# PowerBoard_V04.net
KiCad netlist of a schematic drawn in Altium Designer
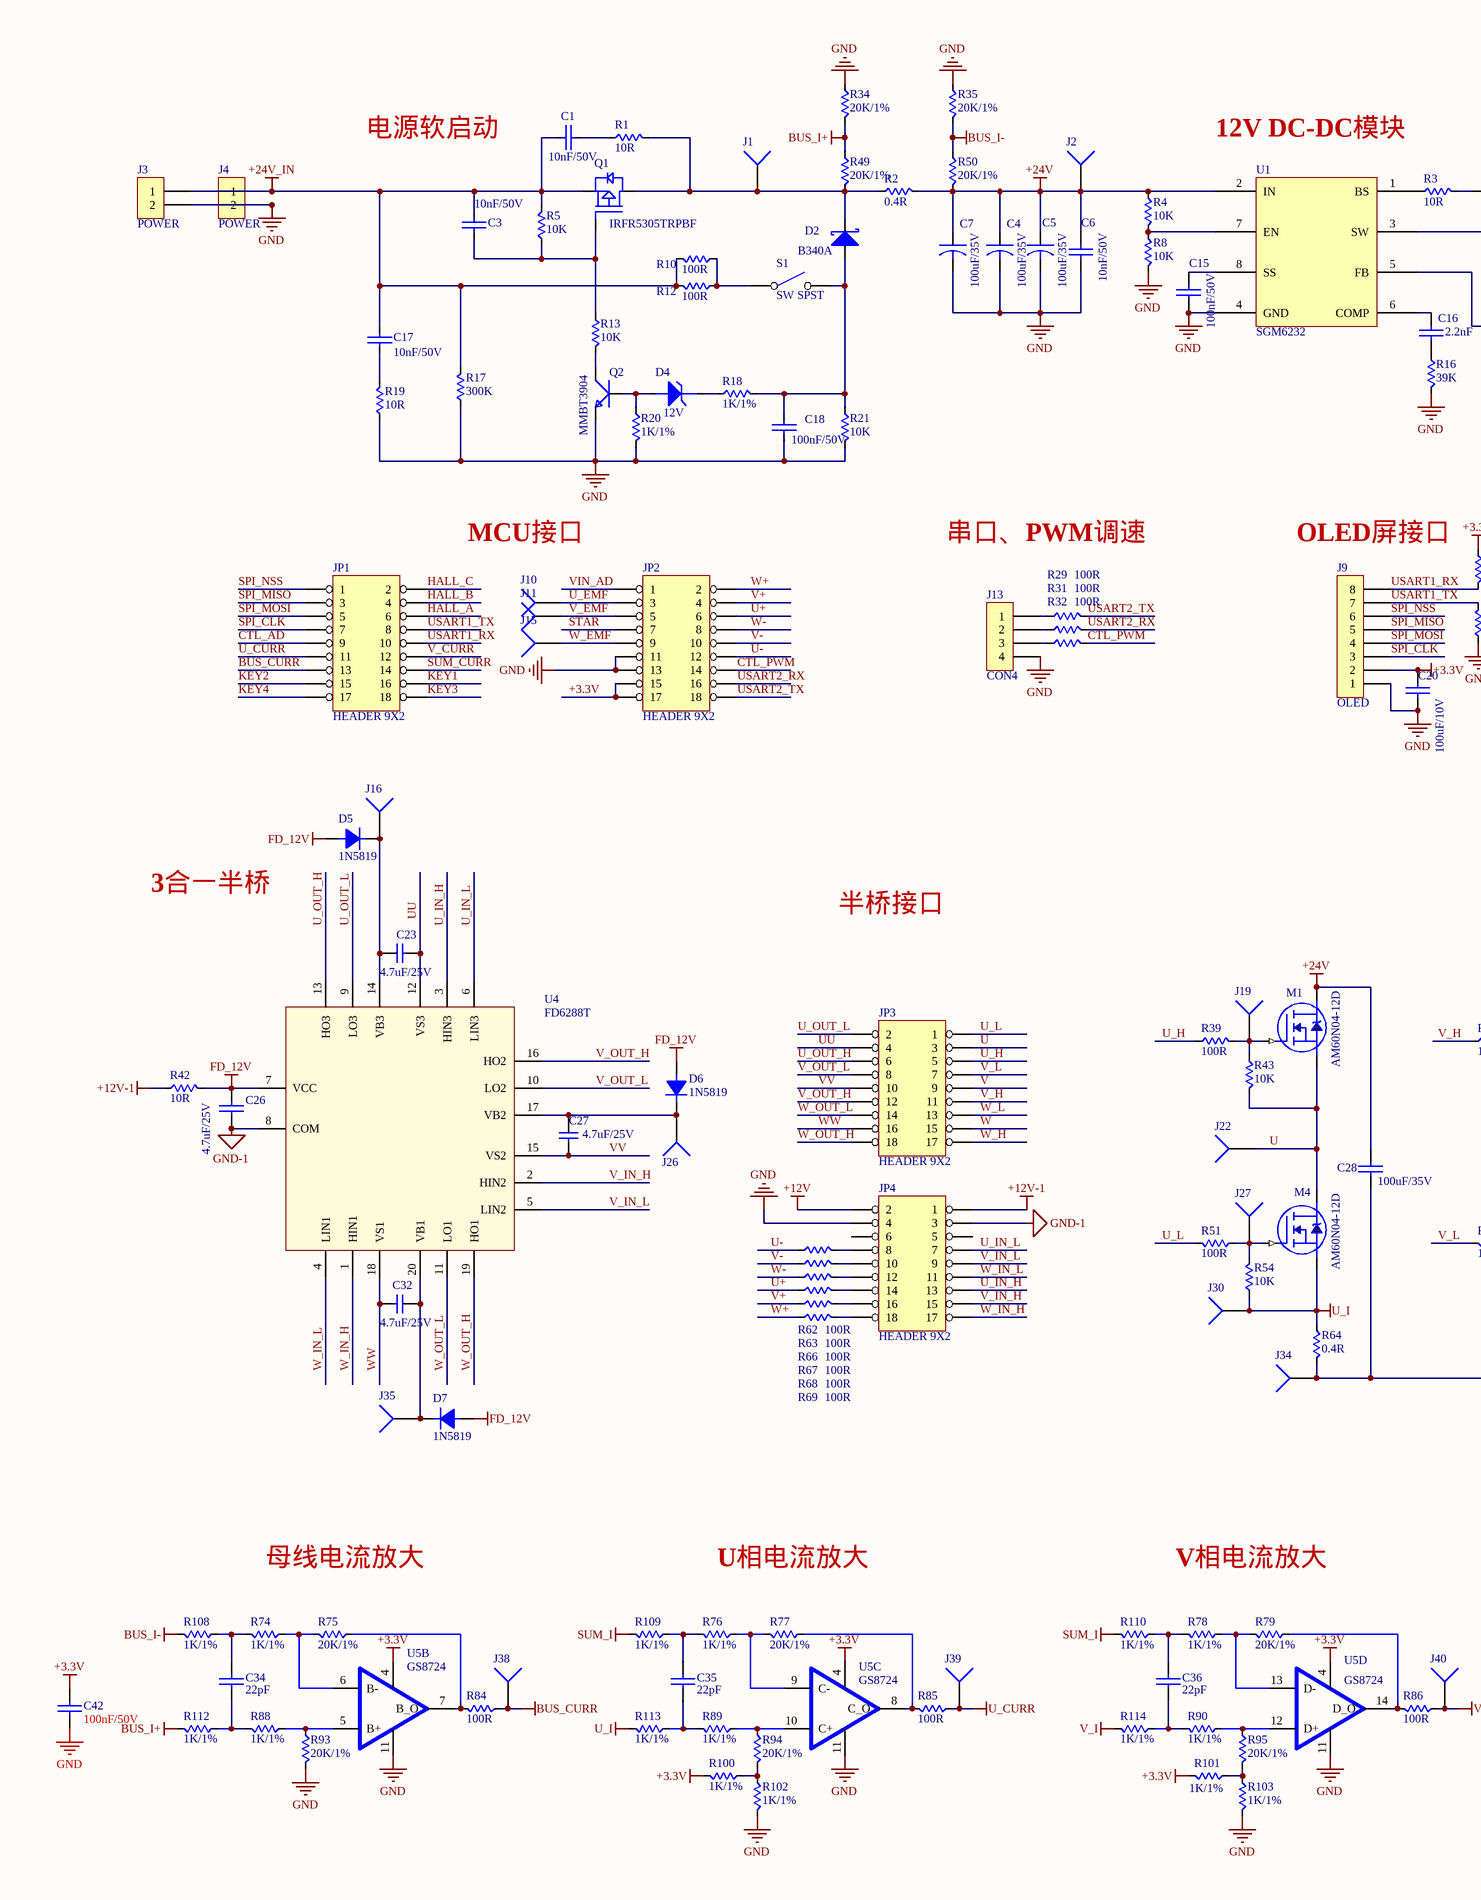
[diagram p0: PowerBoard V04.SchDoc, left]
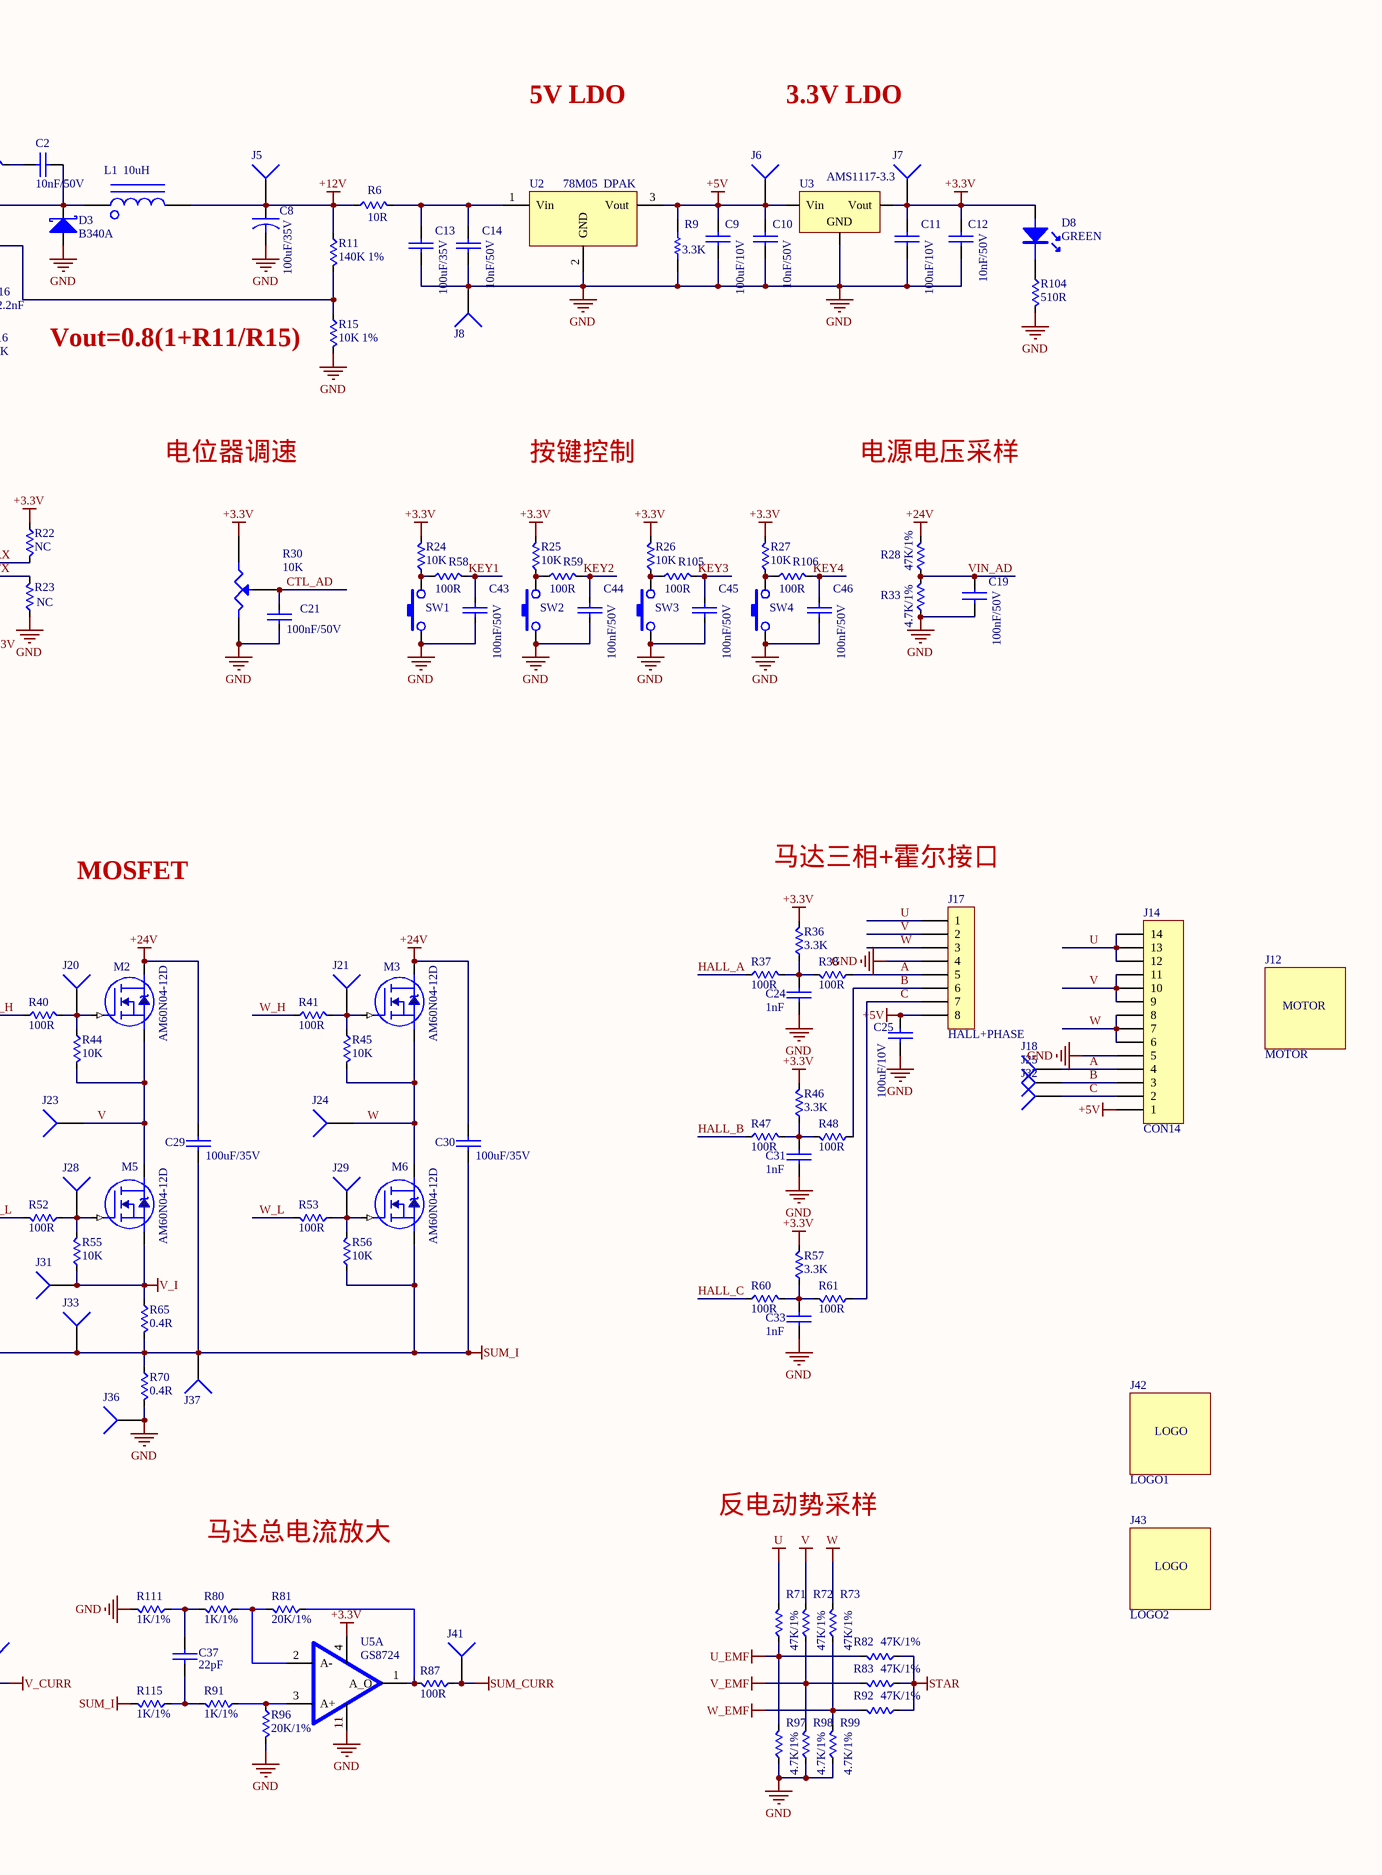
[diagram p1: PowerBoard V04.SchDoc, right]

(export (version "E")
  (design (tool "Eeschema 10.0.6"))
  (components
    (comp (ref "C1")
      (value "10nF/50V")
      (footprint "0603C")
      (description "Capacitor")
      (libsource (lib "") (part "CAP_1"))
    )
    (comp (ref "C2")
      (value "10nF/50V")
      (footprint "0603C")
      (description "Capacitor")
      (libsource (lib "*") (part "CAP"))
    )
    (comp (ref "C3")
      (value "10nF/50V")
      (footprint "0603C")
      (description "Capacitor")
      (libsource (lib "") (part "CAP_1"))
    )
    (comp (ref "C4")
      (value "100uF/35V")
      (footprint "SMD-D")
      (description "Capacitor")
      (libsource (lib "*") (part "CAPACITOR"))
    )
    (comp (ref "C5")
      (value "100uF/35V")
      (footprint "SMD-D")
      (description "Capacitor")
      (libsource (lib "*") (part "CAPACITOR"))
    )
    (comp (ref "C6")
      (value "10nF/50V")
      (footprint "0603C")
      (description "Capacitor")
      (libsource (lib "*") (part "CAP"))
    )
    (comp (ref "C7")
      (value "100uF/35V")
      (footprint "SMD-D")
      (description "Capacitor")
      (libsource (lib "*") (part "CAPACITOR"))
    )
    (comp (ref "C8")
      (value "100uF/35V")
      (footprint "SMD-D")
      (description "Capacitor")
      (libsource (lib "*") (part "CAPACITOR"))
    )
    (comp (ref "C9")
      (value "100uF/10V")
      (footprint "SMD-C")
      (description "Capacitor")
      (libsource (lib "") (part "CAP_2"))
    )
    (comp (ref "C10")
      (value "10nF/50V")
      (footprint "0603C")
      (description "Capacitor")
      (libsource (lib "") (part "CAP_2"))
    )
    (comp (ref "C11")
      (value "100uF/10V")
      (footprint "SMD-C")
      (description "Capacitor")
      (libsource (lib "") (part "CAP_2"))
    )
    (comp (ref "C12")
      (value "10nF/50V")
      (footprint "0603C")
      (description "Capacitor")
      (libsource (lib "") (part "CAP_2"))
    )
    (comp (ref "C13")
      (value "100uF/35V")
      (footprint "SMD-D")
      (description "Capacitor")
      (libsource (lib "") (part "CAP_2"))
    )
    (comp (ref "C14")
      (value "10nF/50V")
      (footprint "0603C")
      (description "Capacitor")
      (libsource (lib "") (part "CAP_2"))
    )
    (comp (ref "C15")
      (value "100nF/50V")
      (footprint "0603C")
      (description "Capacitor")
      (libsource (lib "*") (part "CAP"))
    )
    (comp (ref "C16")
      (value "2.2nF")
      (footprint "0603C")
      (description "Capacitor")
      (libsource (lib "*") (part "CAP"))
    )
    (comp (ref "C17")
      (value "10nF/50V")
      (footprint "0603C")
      (description "Capacitor")
      (libsource (lib "") (part "CAP_1"))
    )
    (comp (ref "C18")
      (value "100nF/50V")
      (footprint "0603C")
      (description "Capacitor")
      (libsource (lib "") (part "CAP_1"))
    )
    (comp (ref "C19")
      (value "100nF/50V")
      (footprint "0603C")
      (description "Y02-02238")
      (libsource (lib "*") (part "CAP NP"))
    )
    (comp (ref "C20")
      (value "100uF/10V")
      (footprint "SMD-C")
      (description "Capacitor")
      (libsource (lib "") (part "CAP_2"))
    )
    (comp (ref "C21")
      (value "100nF/50V")
      (footprint "0603C")
      (description "Capacitor")
      (libsource (lib "") (part "CAP_1"))
    )
    (comp (ref "C23")
      (value "4.7uF/25V")
      (footprint "0805C")
      (description "CAP")
      (libsource (lib "") (part "CAP_3"))
    )
    (comp (ref "C24")
      (value "1nF")
      (footprint "0603C")
      (description "Capacitor")
      (libsource (lib "") (part "CAP_2"))
    )
    (comp (ref "C25")
      (value "100uF/10V")
      (footprint "SMD-C")
      (description "Capacitor")
      (libsource (lib "") (part "CAP_2"))
    )
    (comp (ref "C26")
      (value "4.7uF/25V")
      (footprint "0805C")
      (description "Capacitor")
      (libsource (lib "") (part "CAP_2"))
    )
    (comp (ref "C27")
      (value "4.7uF/25V")
      (footprint "0805C")
      (description "CAP")
      (libsource (lib "") (part "CAP_3"))
    )
    (comp (ref "C28")
      (value "100uF/35V")
      (footprint "SMD-D")
      (description "Capacitor")
      (libsource (lib "") (part "CAP_2"))
    )
    (comp (ref "C29")
      (value "100uF/35V")
      (footprint "SMD-D")
      (description "Capacitor")
      (libsource (lib "") (part "CAP_2"))
    )
    (comp (ref "C30")
      (value "100uF/35V")
      (footprint "SMD-D")
      (description "Capacitor")
      (libsource (lib "") (part "CAP_2"))
    )
    (comp (ref "C31")
      (value "1nF")
      (footprint "0603C")
      (description "Capacitor")
      (libsource (lib "") (part "CAP_2"))
    )
    (comp (ref "C32")
      (value "4.7uF/25V")
      (footprint "0805C")
      (description "CAP")
      (libsource (lib "") (part "CAP_3"))
    )
    (comp (ref "C33")
      (value "1nF")
      (footprint "0603C")
      (description "Capacitor")
      (libsource (lib "") (part "CAP_2"))
    )
    (comp (ref "C34")
      (value "22pF")
      (footprint "0603C")
      (description "Capacitor")
      (libsource (lib "*") (part "CAP"))
    )
    (comp (ref "C35")
      (value "22pF")
      (footprint "0603C")
      (description "Capacitor")
      (libsource (lib "*") (part "CAP"))
    )
    (comp (ref "C36")
      (value "22pF")
      (footprint "0603C")
      (description "Capacitor")
      (libsource (lib "*") (part "CAP"))
    )
    (comp (ref "C37")
      (value "22pF")
      (footprint "0603C")
      (description "Capacitor")
      (libsource (lib "*") (part "CAP"))
    )
    (comp (ref "C42")
      (value "100nF/50V")
      (footprint "0603C")
      (description "Capacitor")
      (libsource (lib "*") (part "CAP"))
    )
    (comp (ref "C43")
      (value "100nF/50V")
      (footprint "0603C")
      (description "Capacitor")
      (libsource (lib "") (part "CAP_1"))
    )
    (comp (ref "C44")
      (value "100nF/50V")
      (footprint "0603C")
      (description "Capacitor")
      (libsource (lib "") (part "CAP_1"))
    )
    (comp (ref "C45")
      (value "100nF/50V")
      (footprint "0603C")
      (description "Capacitor")
      (libsource (lib "") (part "CAP_1"))
    )
    (comp (ref "C46")
      (value "100nF/50V")
      (footprint "0603C")
      (description "Capacitor")
      (libsource (lib "") (part "CAP_1"))
    )
    (comp (ref "D2")
      (value "B340A")
      (footprint "DO214AC(SMA)")
      (description "Schottky Diode")
      (libsource (lib "COFLY-SCH") (part "DIODE SCHOTTKY"))
    )
    (comp (ref "D3")
      (value "B340A")
      (footprint "DO214AC(SMA)")
      (description "Schottky Diode")
      (libsource (lib "COFLY-SCH") (part "DIODE SCHOTTKY"))
    )
    (comp (ref "D4")
      (value "12V")
      (footprint "SOD-123")
      (description "Zener Diode")
      (libsource (lib "*") (part "ZENER3"))
    )
    (comp (ref "D5")
      (value "1N5819")
      (footprint "SOD-123")
      (description "Diode")
      (libsource (lib "*") (part "DIODE"))
    )
    (comp (ref "D6")
      (value "1N5819")
      (footprint "SOD-123")
      (description "Diode")
      (libsource (lib "*") (part "DIODE"))
    )
    (comp (ref "D7")
      (value "1N5819")
      (footprint "SOD-123")
      (description "Diode")
      (libsource (lib "*") (part "DIODE"))
    )
    (comp (ref "D8")
      (value "GREEN")
      (footprint "0603D")
      (description "Y02-01665")
      (libsource (lib "*") (part "LED"))
    )
    (comp (ref "J1")
      (value "~")
      (footprint "PLUG")
      (description "Plug")
      (fields (field (name "PUBLISHER") "Altium Limited"))
      (libsource (lib "Miscellaneous Connectors") (part "Socket"))
    )
    (comp (ref "J2")
      (value "~")
      (footprint "PLUG")
      (description "Plug")
      (fields (field (name "PUBLISHER") "Altium Limited"))
      (libsource (lib "Miscellaneous Connectors") (part "Socket"))
    )
    (comp (ref "J3")
      (value "POWER")
      (footprint "DC")
      (description "Connector")
      (libsource (lib "COFLY-SCH") (part "CON2"))
    )
    (comp (ref "J4")
      (value "POWER")
      (footprint "HEADER 1X2 3.96")
      (description "Connector")
      (libsource (lib "COFLY-SCH") (part "CON2"))
    )
    (comp (ref "J5")
      (value "~")
      (footprint "PLUG")
      (description "Plug")
      (fields (field (name "PUBLISHER") "Altium Limited"))
      (libsource (lib "Miscellaneous Connectors") (part "Socket"))
    )
    (comp (ref "J6")
      (value "~")
      (footprint "PLUG")
      (description "Plug")
      (fields (field (name "PUBLISHER") "Altium Limited"))
      (libsource (lib "Miscellaneous Connectors") (part "Socket"))
    )
    (comp (ref "J7")
      (value "~")
      (footprint "PLUG")
      (description "Plug")
      (fields (field (name "PUBLISHER") "Altium Limited"))
      (libsource (lib "Miscellaneous Connectors") (part "Socket"))
    )
    (comp (ref "J8")
      (value "~")
      (footprint "PLUG")
      (description "Plug")
      (fields (field (name "PUBLISHER") "Altium Limited"))
      (libsource (lib "Miscellaneous Connectors") (part "Socket"))
    )
    (comp (ref "J9")
      (value "OLED")
      (footprint "1.8_SPI_TFT_NC")
      (description "Connector")
      (libsource (lib "") (part "CON8_1"))
    )
    (comp (ref "J10")
      (value "~")
      (footprint "PLUG")
      (description "Plug")
      (fields (field (name "PUBLISHER") "Altium Limited"))
      (libsource (lib "Miscellaneous Connectors") (part "Socket"))
    )
    (comp (ref "J11")
      (value "~")
      (footprint "PLUG")
      (description "Plug")
      (fields (field (name "PUBLISHER") "Altium Limited"))
      (libsource (lib "Miscellaneous Connectors") (part "Socket"))
    )
    (comp (ref "J12") (value "MOTOR") (footprint "HALL_MOTOR") (libsource (lib "COFLY-SCH") (part "MOTOR")))
    (comp (ref "J13")
      (value "CON4")
      (footprint "SIP4")
      (description "Connector")
      (libsource (lib "COFLY-SCH") (part "CON4"))
    )
    (comp (ref "J14")
      (value "CON14")
      (footprint "FPC_XF2M-1415-1A")
      (description "Connector")
      (libsource (lib "COFLY-SCH") (part "CON14"))
    )
    (comp (ref "J15")
      (value "~")
      (footprint "PLUG")
      (description "Plug")
      (fields (field (name "PUBLISHER") "Altium Limited"))
      (libsource (lib "Miscellaneous Connectors") (part "Socket"))
    )
    (comp (ref "J16")
      (value "~")
      (footprint "PLUG")
      (description "Plug")
      (fields (field (name "PUBLISHER") "Altium Limited"))
      (libsource (lib "Miscellaneous Connectors") (part "Socket"))
    )
    (comp (ref "J17")
      (value "HALL+PHASE")
      (footprint "HEADER 1X8 3.96")
      (description "Connector")
      (libsource (lib "COFLY-SCH") (part "CON8"))
    )
    (comp (ref "J18")
      (value "~")
      (footprint "PLUG")
      (description "Plug")
      (fields (field (name "PUBLISHER") "Altium Limited"))
      (libsource (lib "Miscellaneous Connectors") (part "Socket"))
    )
    (comp (ref "J19")
      (value "~")
      (footprint "PLUG")
      (description "Plug")
      (fields (field (name "PUBLISHER") "Altium Limited"))
      (libsource (lib "Miscellaneous Connectors") (part "Socket"))
    )
    (comp (ref "J20")
      (value "~")
      (footprint "PLUG")
      (description "Plug")
      (fields (field (name "PUBLISHER") "Altium Limited"))
      (libsource (lib "Miscellaneous Connectors") (part "Socket"))
    )
    (comp (ref "J21")
      (value "~")
      (footprint "PLUG")
      (description "Plug")
      (fields (field (name "PUBLISHER") "Altium Limited"))
      (libsource (lib "Miscellaneous Connectors") (part "Socket"))
    )
    (comp (ref "J22")
      (value "~")
      (footprint "PLUG")
      (description "Plug")
      (fields (field (name "PUBLISHER") "Altium Limited"))
      (libsource (lib "Miscellaneous Connectors") (part "Socket"))
    )
    (comp (ref "J23")
      (value "~")
      (footprint "PLUG")
      (description "Plug")
      (fields (field (name "PUBLISHER") "Altium Limited"))
      (libsource (lib "Miscellaneous Connectors") (part "Socket"))
    )
    (comp (ref "J24")
      (value "~")
      (footprint "PLUG")
      (description "Plug")
      (fields (field (name "PUBLISHER") "Altium Limited"))
      (libsource (lib "Miscellaneous Connectors") (part "Socket"))
    )
    (comp (ref "J25")
      (value "~")
      (footprint "PLUG")
      (description "Plug")
      (fields (field (name "PUBLISHER") "Altium Limited"))
      (libsource (lib "Miscellaneous Connectors") (part "Socket"))
    )
    (comp (ref "J26")
      (value "~")
      (footprint "PLUG")
      (description "Plug")
      (fields (field (name "PUBLISHER") "Altium Limited"))
      (libsource (lib "Miscellaneous Connectors") (part "Socket"))
    )
    (comp (ref "J27")
      (value "~")
      (footprint "PLUG")
      (description "Plug")
      (fields (field (name "PUBLISHER") "Altium Limited"))
      (libsource (lib "Miscellaneous Connectors") (part "Socket"))
    )
    (comp (ref "J28")
      (value "~")
      (footprint "PLUG")
      (description "Plug")
      (fields (field (name "PUBLISHER") "Altium Limited"))
      (libsource (lib "Miscellaneous Connectors") (part "Socket"))
    )
    (comp (ref "J29")
      (value "~")
      (footprint "PLUG")
      (description "Plug")
      (fields (field (name "PUBLISHER") "Altium Limited"))
      (libsource (lib "Miscellaneous Connectors") (part "Socket"))
    )
    (comp (ref "J30")
      (value "~")
      (footprint "PLUG")
      (description "Plug")
      (fields (field (name "PUBLISHER") "Altium Limited"))
      (libsource (lib "Miscellaneous Connectors") (part "Socket"))
    )
    (comp (ref "J31")
      (value "~")
      (footprint "PLUG")
      (description "Plug")
      (fields (field (name "PUBLISHER") "Altium Limited"))
      (libsource (lib "Miscellaneous Connectors") (part "Socket"))
    )
    (comp (ref "J32")
      (value "~")
      (footprint "PLUG")
      (description "Plug")
      (fields (field (name "PUBLISHER") "Altium Limited"))
      (libsource (lib "Miscellaneous Connectors") (part "Socket"))
    )
    (comp (ref "J33")
      (value "~")
      (footprint "PLUG")
      (description "Plug")
      (fields (field (name "PUBLISHER") "Altium Limited"))
      (libsource (lib "Miscellaneous Connectors") (part "Socket"))
    )
    (comp (ref "J34")
      (value "~")
      (footprint "PLUG")
      (description "Plug")
      (fields (field (name "PUBLISHER") "Altium Limited"))
      (libsource (lib "Miscellaneous Connectors") (part "Socket"))
    )
    (comp (ref "J35")
      (value "~")
      (footprint "PLUG")
      (description "Plug")
      (fields (field (name "PUBLISHER") "Altium Limited"))
      (libsource (lib "Miscellaneous Connectors") (part "Socket"))
    )
    (comp (ref "J36")
      (value "~")
      (footprint "PLUG")
      (description "Plug")
      (fields (field (name "PUBLISHER") "Altium Limited"))
      (libsource (lib "Miscellaneous Connectors") (part "Socket"))
    )
    (comp (ref "J37")
      (value "~")
      (footprint "PLUG")
      (description "Plug")
      (fields (field (name "PUBLISHER") "Altium Limited"))
      (libsource (lib "Miscellaneous Connectors") (part "Socket"))
    )
    (comp (ref "J38")
      (value "~")
      (footprint "PLUG")
      (description "Plug")
      (fields (field (name "PUBLISHER") "Altium Limited"))
      (libsource (lib "Miscellaneous Connectors") (part "Socket"))
    )
    (comp (ref "J39")
      (value "~")
      (footprint "PLUG")
      (description "Plug")
      (fields (field (name "PUBLISHER") "Altium Limited"))
      (libsource (lib "Miscellaneous Connectors") (part "Socket"))
    )
    (comp (ref "J40")
      (value "~")
      (footprint "PLUG")
      (description "Plug")
      (fields (field (name "PUBLISHER") "Altium Limited"))
      (libsource (lib "Miscellaneous Connectors") (part "Socket"))
    )
    (comp (ref "J41")
      (value "~")
      (footprint "PLUG")
      (description "Plug")
      (fields (field (name "PUBLISHER") "Altium Limited"))
      (libsource (lib "Miscellaneous Connectors") (part "Socket"))
    )
    (comp (ref "J42")
      (value "LOGO1")
      (footprint "LOGO-ZHANGFEI")
      (description "LOGO")
      (libsource (lib "COFLY-SCH") (part "LOGO"))
    )
    (comp (ref "J43")
      (value "LOGO2")
      (footprint "LOGO_WENWEN")
      (description "LOGO")
      (libsource (lib "COFLY-SCH") (part "LOGO"))
    )
    (comp (ref "JP1")
      (value "HEADER 9X2")
      (footprint "SMT2.54-2X9-F")
      (libsource (lib "") (part "HEADER 9X2_1"))
    )
    (comp (ref "JP2")
      (value "HEADER 9X2")
      (footprint "SMT2.54-2X9-F")
      (libsource (lib "") (part "HEADER 9X2_1"))
    )
    (comp (ref "JP3")
      (value "HEADER 9X2")
      (footprint "SMT2.54-2X9-M")
      (libsource (lib "COFLY-SCH") (part "HEADER 9X2"))
    )
    (comp (ref "JP4")
      (value "HEADER 9X2")
      (footprint "SMT2.54-2X9-M")
      (libsource (lib "COFLY-SCH") (part "HEADER 9X2"))
    )
    (comp (ref "L1") (value "10uH") (footprint "CSAB0730-220M") (libsource (lib "*") (part "INDUCTOR IRON1")))
    (comp (ref "M1")
      (value "AM60N04-12D")
      (footprint "DPAK")
      (description "Low Charge N-Channel MOSFET")
      (libsource (lib "*") (part "MOSFEN"))
    )
    (comp (ref "M2")
      (value "AM60N04-12D")
      (footprint "DPAK")
      (description "Low Charge N-Channel MOSFET")
      (libsource (lib "*") (part "MOSFEN"))
    )
    (comp (ref "M3")
      (value "AM60N04-12D")
      (footprint "DPAK")
      (description "Low Charge N-Channel MOSFET")
      (libsource (lib "*") (part "MOSFEN"))
    )
    (comp (ref "M4")
      (value "AM60N04-12D")
      (footprint "DPAK")
      (description "Low Charge N-Channel MOSFET")
      (libsource (lib "*") (part "MOSFEN"))
    )
    (comp (ref "M5")
      (value "AM60N04-12D")
      (footprint "DPAK")
      (description "Low Charge N-Channel MOSFET")
      (libsource (lib "*") (part "MOSFEN"))
    )
    (comp (ref "M6")
      (value "AM60N04-12D")
      (footprint "DPAK")
      (description "Low Charge N-Channel MOSFET")
      (libsource (lib "*") (part "MOSFEN"))
    )
    (comp (ref "Q1")
      (value "IRFR5305TRPBF")
      (footprint "DPAK")
      (libsource (lib "COFLY-SCH") (part "MOSFET P"))
    )
    (comp (ref "Q2")
      (value "MMBT3904")
      (footprint "SOT-23A")
      (description "NPN")
      (libsource (lib "*") (part "NPN(BEC)"))
    )
    (comp (ref "R1") (value "10R") (footprint "0603R") (libsource (lib "COFLY-SCH") (part "RES")))
    (comp (ref "R2") (value "0.4R") (footprint "2512S") (libsource (lib "COFLY-SCH") (part "RES")))
    (comp (ref "R3") (value "10R") (footprint "0603R") (libsource (lib "COFLY-SCH") (part "RES")))
    (comp (ref "R4") (value "10K") (footprint "0603R") (libsource (lib "COFLY-SCH") (part "RES")))
    (comp (ref "R5") (value "10K") (footprint "0603R") (libsource (lib "COFLY-SCH") (part "RES")))
    (comp (ref "R6") (value "10R") (footprint "1206R") (libsource (lib "COFLY-SCH") (part "RES")))
    (comp (ref "R8") (value "10K") (footprint "0603R") (libsource (lib "COFLY-SCH") (part "RES")))
    (comp (ref "R9")
      (value "3.3K")
      (footprint "0603R")
      (description "Semiconductor Resistor")
      (fields
        (field (name "MANUFACTURER") "Generic Components")
        (field (name "PUBLISHER") "Altium Hobart Technology Centre")
      )
      (libsource (lib "*") (part "Res Semi"))
    )
    (comp (ref "R10") (value "100R") (footprint "1206R") (libsource (lib "COFLY-SCH") (part "RES")))
    (comp (ref "R11") (value "140K 1%") (footprint "0603r") (libsource (lib "COFLY-SCH") (part "RES")))
    (comp (ref "R12") (value "100R") (footprint "1206R") (libsource (lib "COFLY-SCH") (part "RES")))
    (comp (ref "R13") (value "10K") (footprint "0603R") (libsource (lib "COFLY-SCH") (part "RES")))
    (comp (ref "R15") (value "10K 1%") (footprint "0603R") (libsource (lib "COFLY-SCH") (part "RES")))
    (comp (ref "R16") (value "39K") (footprint "0603R") (libsource (lib "COFLY-SCH") (part "RES")))
    (comp (ref "R17") (value "300K") (footprint "0603R") (libsource (lib "COFLY-SCH") (part "RES")))
    (comp (ref "R18") (value "1K/1%") (footprint "0603R") (libsource (lib "COFLY-SCH") (part "RES")))
    (comp (ref "R19") (value "10R") (footprint "0603R") (libsource (lib "COFLY-SCH") (part "RES")))
    (comp (ref "R20") (value "1K/1%") (footprint "0603R") (libsource (lib "COFLY-SCH") (part "RES")))
    (comp (ref "R21") (value "10K") (footprint "0603R") (libsource (lib "COFLY-SCH") (part "RES")))
    (comp (ref "R22")
      (value "NC")
      (footprint "0603R")
      (description "Y02-00588")
      (libsource (lib "*") (part "RES"))
    )
    (comp (ref "R23")
      (value "NC")
      (footprint "0603R")
      (description "Y02-01715")
      (libsource (lib "*") (part "RES"))
    )
    (comp (ref "R24") (value "10K") (footprint "0603R") (libsource (lib "*") (part "RES")))
    (comp (ref "R25") (value "10K") (footprint "0603R") (libsource (lib "*") (part "RES")))
    (comp (ref "R26") (value "10K") (footprint "0603R") (libsource (lib "*") (part "RES")))
    (comp (ref "R27") (value "10K") (footprint "0603R") (libsource (lib "*") (part "RES")))
    (comp (ref "R28")
      (value "47K/1%")
      (footprint "0603R")
      (description "Y02-00588")
      (libsource (lib "*") (part "RES"))
    )
    (comp (ref "R29") (value "100R") (footprint "0603R") (libsource (lib "COFLY-SCH") (part "RES")))
    (comp (ref "R30")
      (value "10K")
      (footprint "B10K-9MM")
      (description "Potentiometer")
      (libsource (lib "COFLY-SCH") (part "POT1"))
    )
    (comp (ref "R31") (value "100R") (footprint "0603R") (libsource (lib "COFLY-SCH") (part "RES")))
    (comp (ref "R32") (value "100R") (footprint "0603R") (libsource (lib "COFLY-SCH") (part "RES")))
    (comp (ref "R33")
      (value "4.7K/1%")
      (footprint "0603R")
      (description "Y02-01715")
      (libsource (lib "*") (part "RES"))
    )
    (comp (ref "R34") (value "20K/1%") (footprint "0603R") (libsource (lib "*") (part "RES")))
    (comp (ref "R35") (value "20K/1%") (footprint "0603R") (libsource (lib "*") (part "RES")))
    (comp (ref "R36") (value "3.3K") (footprint "0603R") (libsource (lib "COFLY-SCH") (part "RES")))
    (comp (ref "R37") (value "100R") (footprint "0603R") (libsource (lib "COFLY-SCH") (part "RES")))
    (comp (ref "R38") (value "100R") (footprint "0603R") (libsource (lib "COFLY-SCH") (part "RES")))
    (comp (ref "R39") (value "100R") (footprint "0603R") (libsource (lib "COFLY-SCH") (part "RES")))
    (comp (ref "R40") (value "100R") (footprint "0603R") (libsource (lib "COFLY-SCH") (part "RES")))
    (comp (ref "R41") (value "100R") (footprint "0603R") (libsource (lib "COFLY-SCH") (part "RES")))
    (comp (ref "R42") (value "10R") (footprint "1206r") (libsource (lib "*") (part "RES")))
    (comp (ref "R43") (value "10K") (footprint "0603R") (libsource (lib "COFLY-SCH") (part "RES")))
    (comp (ref "R44") (value "10K") (footprint "0603R") (libsource (lib "COFLY-SCH") (part "RES")))
    (comp (ref "R45") (value "10K") (footprint "0603R") (libsource (lib "COFLY-SCH") (part "RES")))
    (comp (ref "R46") (value "3.3K") (footprint "0603R") (libsource (lib "COFLY-SCH") (part "RES")))
    (comp (ref "R47") (value "100R") (footprint "0603R") (libsource (lib "COFLY-SCH") (part "RES")))
    (comp (ref "R48") (value "100R") (footprint "0603R") (libsource (lib "COFLY-SCH") (part "RES")))
    (comp (ref "R49") (value "20K/1%") (footprint "0603R") (libsource (lib "*") (part "RES")))
    (comp (ref "R50") (value "20K/1%") (footprint "0603R") (libsource (lib "*") (part "RES")))
    (comp (ref "R51") (value "100R") (footprint "0603R") (libsource (lib "COFLY-SCH") (part "RES")))
    (comp (ref "R52") (value "100R") (footprint "0603R") (libsource (lib "COFLY-SCH") (part "RES")))
    (comp (ref "R53") (value "100R") (footprint "0603R") (libsource (lib "COFLY-SCH") (part "RES")))
    (comp (ref "R54") (value "10K") (footprint "0603R") (libsource (lib "COFLY-SCH") (part "RES")))
    (comp (ref "R55") (value "10K") (footprint "0603R") (libsource (lib "COFLY-SCH") (part "RES")))
    (comp (ref "R56") (value "10K") (footprint "0603R") (libsource (lib "COFLY-SCH") (part "RES")))
    (comp (ref "R57") (value "3.3K") (footprint "0603R") (libsource (lib "COFLY-SCH") (part "RES")))
    (comp (ref "R58") (value "100R") (footprint "0603R") (libsource (lib "COFLY-SCH") (part "RES")))
    (comp (ref "R59") (value "100R") (footprint "0603R") (libsource (lib "COFLY-SCH") (part "RES")))
    (comp (ref "R60") (value "100R") (footprint "0603R") (libsource (lib "COFLY-SCH") (part "RES")))
    (comp (ref "R61") (value "100R") (footprint "0603R") (libsource (lib "COFLY-SCH") (part "RES")))
    (comp (ref "R62") (value "100R") (footprint "0603R") (libsource (lib "*") (part "RES")))
    (comp (ref "R63") (value "100R") (footprint "0603R") (libsource (lib "*") (part "RES")))
    (comp (ref "R64") (value "0.4R") (footprint "2512S") (libsource (lib "COFLY-SCH") (part "RES")))
    (comp (ref "R65") (value "0.4R") (footprint "2512S") (libsource (lib "COFLY-SCH") (part "RES")))
    (comp (ref "R66") (value "100R") (footprint "0603R") (libsource (lib "*") (part "RES")))
    (comp (ref "R67") (value "100R") (footprint "0603R") (libsource (lib "*") (part "RES")))
    (comp (ref "R68") (value "100R") (footprint "0603R") (libsource (lib "*") (part "RES")))
    (comp (ref "R69") (value "100R") (footprint "0603R") (libsource (lib "*") (part "RES")))
    (comp (ref "R70") (value "0.4R") (footprint "2512S") (libsource (lib "COFLY-SCH") (part "RES")))
    (comp (ref "R71")
      (value "47K/1%")
      (footprint "0603R")
      (description "Y02-00588")
      (libsource (lib "*") (part "RES"))
    )
    (comp (ref "R72")
      (value "47K/1%")
      (footprint "0603R")
      (description "Y02-00588")
      (libsource (lib "*") (part "RES"))
    )
    (comp (ref "R73")
      (value "47K/1%")
      (footprint "0603R")
      (description "Y02-00588")
      (libsource (lib "*") (part "RES"))
    )
    (comp (ref "R74") (value "1K/1%") (footprint "0603R") (libsource (lib "*") (part "RES")))
    (comp (ref "R75") (value "20K/1%") (footprint "0603R") (libsource (lib "*") (part "RES")))
    (comp (ref "R76") (value "1K/1%") (footprint "0603R") (libsource (lib "*") (part "RES")))
    (comp (ref "R77") (value "20K/1%") (footprint "0603R") (libsource (lib "*") (part "RES")))
    (comp (ref "R78") (value "1K/1%") (footprint "0603R") (libsource (lib "*") (part "RES")))
    (comp (ref "R79") (value "20K/1%") (footprint "0603R") (libsource (lib "*") (part "RES")))
    (comp (ref "R80") (value "1K/1%") (footprint "0603R") (libsource (lib "*") (part "RES")))
    (comp (ref "R81") (value "20K/1%") (footprint "0603R") (libsource (lib "*") (part "RES")))
    (comp (ref "R82")
      (value "47K/1%")
      (footprint "0603R")
      (description "Y02-00588")
      (libsource (lib "*") (part "RES"))
    )
    (comp (ref "R83")
      (value "47K/1%")
      (footprint "0603R")
      (description "Y02-00588")
      (libsource (lib "*") (part "RES"))
    )
    (comp (ref "R84") (value "100R") (footprint "0603R") (libsource (lib "*") (part "RES")))
    (comp (ref "R85") (value "100R") (footprint "0603R") (libsource (lib "*") (part "RES")))
    (comp (ref "R86") (value "100R") (footprint "0603R") (libsource (lib "*") (part "RES")))
    (comp (ref "R87") (value "100R") (footprint "0603R") (libsource (lib "*") (part "RES")))
    (comp (ref "R88") (value "1K/1%") (footprint "0603R") (libsource (lib "*") (part "RES")))
    (comp (ref "R89") (value "1K/1%") (footprint "0603R") (libsource (lib "*") (part "RES")))
    (comp (ref "R90") (value "1K/1%") (footprint "0603R") (libsource (lib "*") (part "RES")))
    (comp (ref "R91") (value "1K/1%") (footprint "0603R") (libsource (lib "*") (part "RES")))
    (comp (ref "R92")
      (value "47K/1%")
      (footprint "0603R")
      (description "Y02-00588")
      (libsource (lib "*") (part "RES"))
    )
    (comp (ref "R93") (value "20K/1%") (footprint "0603R") (libsource (lib "*") (part "RES")))
    (comp (ref "R94") (value "20K/1%") (footprint "0603R") (libsource (lib "*") (part "RES")))
    (comp (ref "R95") (value "20K/1%") (footprint "0603R") (libsource (lib "*") (part "RES")))
    (comp (ref "R96") (value "20K/1%") (footprint "0603R") (libsource (lib "*") (part "RES")))
    (comp (ref "R97")
      (value "4.7K/1%")
      (footprint "0603R")
      (description "Y02-01715")
      (libsource (lib "*") (part "RES"))
    )
    (comp (ref "R98")
      (value "4.7K/1%")
      (footprint "0603R")
      (description "Y02-01715")
      (libsource (lib "*") (part "RES"))
    )
    (comp (ref "R99")
      (value "4.7K/1%")
      (footprint "0603R")
      (description "Y02-01715")
      (libsource (lib "*") (part "RES"))
    )
    (comp (ref "R100") (value "1K/1%") (footprint "0603R") (libsource (lib "*") (part "RES")))
    (comp (ref "R101") (value "1K/1%") (footprint "0603R") (libsource (lib "*") (part "RES")))
    (comp (ref "R102") (value "1K/1%") (footprint "0603R") (libsource (lib "*") (part "RES")))
    (comp (ref "R103") (value "1K/1%") (footprint "0603R") (libsource (lib "*") (part "RES")))
    (comp (ref "R104")
      (value "510R")
      (footprint "0603R")
      (description "Y02-00493")
      (libsource (lib "YUNEEC-SCH") (part "RES"))
    )
    (comp (ref "R105") (value "100R") (footprint "0603R") (libsource (lib "COFLY-SCH") (part "RES")))
    (comp (ref "R106") (value "100R") (footprint "0603R") (libsource (lib "COFLY-SCH") (part "RES")))
    (comp (ref "R108") (value "1K/1%") (footprint "0603R") (libsource (lib "*") (part "RES")))
    (comp (ref "R109") (value "1K/1%") (footprint "0603R") (libsource (lib "*") (part "RES")))
    (comp (ref "R110") (value "1K/1%") (footprint "0603R") (libsource (lib "*") (part "RES")))
    (comp (ref "R111") (value "1K/1%") (footprint "0603R") (libsource (lib "*") (part "RES")))
    (comp (ref "R112") (value "1K/1%") (footprint "0603R") (libsource (lib "*") (part "RES")))
    (comp (ref "R113") (value "1K/1%") (footprint "0603R") (libsource (lib "*") (part "RES")))
    (comp (ref "R114") (value "1K/1%") (footprint "0603R") (libsource (lib "*") (part "RES")))
    (comp (ref "R115") (value "1K/1%") (footprint "0603R") (libsource (lib "*") (part "RES")))
    (comp (ref "S1") (value "SW SPST") (footprint "SW 2P2T") (libsource (lib "COFLY-SCH") (part "SW SPST")))
    (comp (ref "SW1")
      (value "SW_SW1")
      (footprint "SW6.5*4.5-SMD")
      (description "轻触按键")
      (libsource (lib "Mirarobot_SCH") (part "SW_SW1"))
    )
    (comp (ref "SW2")
      (value "SW_SW1")
      (footprint "SW6.5*4.5-SMD")
      (description "轻触按键")
      (libsource (lib "Mirarobot_SCH") (part "SW_SW1"))
    )
    (comp (ref "SW3")
      (value "SW_SW1")
      (footprint "SW6.5*4.5-SMD")
      (description "轻触按键")
      (libsource (lib "Mirarobot_SCH") (part "SW_SW1"))
    )
    (comp (ref "SW4")
      (value "SW_SW1")
      (footprint "SW6.5*4.5-SMD")
      (description "轻触按键")
      (libsource (lib "Mirarobot_SCH") (part "SW_SW1"))
    )
    (comp (ref "U1") (value "SGM6232") (footprint "SO-8B") (libsource (lib "COFLY-SCH") (part "SGM6232")))
    (comp (ref "U2") (value "78M05  DPAK") (footprint "DPAK") (libsource (lib "*") (part "VOLTREG")))
    (comp (ref "U3")
      (value "AMS1117-3.3")
      (footprint "SOT-223A")
      (description "Voltage Regulator")
      (fields (field (name "PUBLISHER") "*"))
      (libsource (lib "*") (part "Volt Reg"))
    )
    (comp (ref "U4") (value "FD6288T") (footprint "TSSOP-20") (libsource (lib "COFLY-SCH") (part "FD6288T")))
    (comp (ref "U5")
      (value "GS8724")
      (footprint "SO-14A")
      (description "TP2274")
      (libsource (lib "*") (part "TP2274"))
    )
  )
  (nets
    (net (code "1") (name "+3.3V") (class "Default")
      (node (ref "C11") (pin "1") (pinfunction "1_1") (pintype "passive"))
      (node (ref "C12") (pin "1") (pinfunction "1_1") (pintype "passive"))
      (node (ref "C20") (pin "1") (pinfunction "1_1") (pintype "passive"))
      (node (ref "C42") (pin "2") (pinfunction "2_2") (pintype "passive"))
      (node (ref "D8") (pin "1") (pinfunction "1_1") (pintype "passive"))
      (node (ref "J7") (pin "1") (pinfunction "1_1") (pintype "passive"))
      (node (ref "J9") (pin "2") (pinfunction "2_2") (pintype "passive"))
      (node (ref "JP2") (pin "15") (pinfunction "15_15") (pintype "passive"))
      (node (ref "JP2") (pin "17") (pinfunction "17_17") (pintype "passive"))
      (node (ref "R100") (pin "2") (pinfunction "2_2") (pintype "passive"))
      (node (ref "R101") (pin "2") (pinfunction "2_2") (pintype "passive"))
      (node (ref "R22") (pin "2") (pinfunction "2_2") (pintype "passive"))
      (node (ref "R24") (pin "1") (pinfunction "1_1") (pintype "passive"))
      (node (ref "R25") (pin "1") (pinfunction "1_1") (pintype "passive"))
      (node (ref "R26") (pin "1") (pinfunction "1_1") (pintype "passive"))
      (node (ref "R27") (pin "1") (pinfunction "1_1") (pintype "passive"))
      (node (ref "R30") (pin "3") (pinfunction "3_3") (pintype "passive"))
      (node (ref "R36") (pin "2") (pinfunction "2_2") (pintype "passive"))
      (node (ref "R46") (pin "2") (pinfunction "2_2") (pintype "passive"))
      (node (ref "R57") (pin "2") (pinfunction "2_2") (pintype "passive"))
      (node (ref "U3") (pin "2") (pinfunction "Vout_2") (pintype "passive"))
      (node (ref "U5") (pin "4") (pinfunction "VS+_4") (pintype "passive"))
    )
    (net (code "2") (name "+5V") (class "Default")
      (node (ref "C10") (pin "1") (pinfunction "1_1") (pintype "passive"))
      (node (ref "C25") (pin "1") (pinfunction "1_1") (pintype "passive"))
      (node (ref "C9") (pin "1") (pinfunction "1_1") (pintype "passive"))
      (node (ref "J14") (pin "1") (pinfunction "1_1") (pintype "passive"))
      (node (ref "J17") (pin "8") (pinfunction "8_8") (pintype "passive"))
      (node (ref "J6") (pin "1") (pinfunction "1_1") (pintype "passive"))
      (node (ref "R9") (pin "2") (pinfunction "2_2") (pintype "passive"))
      (node (ref "U2") (pin "3") (pinfunction "Vout_3") (pintype "passive"))
      (node (ref "U3") (pin "3") (pinfunction "Vin_3") (pintype "passive"))
    )
    (net (code "3") (name "+12V") (class "Default")
      (node (ref "C8") (pin "1") (pinfunction "1_1") (pintype "passive"))
      (node (ref "J5") (pin "1") (pinfunction "1_1") (pintype "passive"))
      (node (ref "JP4") (pin "2") (pinfunction "2_2") (pintype "passive"))
      (node (ref "L1") (pin "2") (pinfunction "2_2") (pintype "passive"))
      (node (ref "R11") (pin "1") (pinfunction "1_1") (pintype "passive"))
      (node (ref "R6") (pin "1") (pinfunction "1_1") (pintype "passive"))
    )
    (net (code "4") (name "+12V-1") (class "Default")
      (node (ref "JP4") (pin "1") (pinfunction "1_1") (pintype "passive"))
      (node (ref "R42") (pin "1") (pinfunction "1_1") (pintype "passive"))
    )
    (net (code "5") (name "+24V") (class "Default")
      (node (ref "C28") (pin "1") (pinfunction "1_1") (pintype "passive"))
      (node (ref "C29") (pin "1") (pinfunction "1_1") (pintype "passive"))
      (node (ref "C30") (pin "1") (pinfunction "1_1") (pintype "passive"))
      (node (ref "C4") (pin "1") (pinfunction "1_1") (pintype "passive"))
      (node (ref "C5") (pin "1") (pinfunction "1_1") (pintype "passive"))
      (node (ref "C6") (pin "1") (pinfunction "1_1") (pintype "passive"))
      (node (ref "C7") (pin "1") (pinfunction "1_1") (pintype "passive"))
      (node (ref "J2") (pin "1") (pinfunction "1_1") (pintype "passive"))
      (node (ref "M1") (pin "2") (pinfunction "DRAIN_2") (pintype "passive"))
      (node (ref "M2") (pin "2") (pinfunction "DRAIN_2") (pintype "passive"))
      (node (ref "M3") (pin "2") (pinfunction "DRAIN_2") (pintype "passive"))
      (node (ref "R2") (pin "2") (pinfunction "2_2") (pintype "passive"))
      (node (ref "R28") (pin "1") (pinfunction "1_1") (pintype "passive"))
      (node (ref "R4") (pin "1") (pinfunction "1_1") (pintype "passive"))
      (node (ref "R50") (pin "2") (pinfunction "2_2") (pintype "passive"))
      (node (ref "U1") (pin "2") (pinfunction "IN_2") (pintype "passive"))
    )
    (net (code "6") (name "+24V_IN") (class "Default")
      (node (ref "C1") (pin "1") (pinfunction "1_1") (pintype "passive"))
      (node (ref "C17") (pin "2") (pinfunction "2_2") (pintype "passive"))
      (node (ref "C3") (pin "2") (pinfunction "2_2") (pintype "passive"))
      (node (ref "J3") (pin "1") (pinfunction "1_1") (pintype "passive"))
      (node (ref "J4") (pin "1") (pinfunction "1_1") (pintype "passive"))
      (node (ref "Q1") (pin "3") (pinfunction "S_3") (pintype "passive"))
      (node (ref "R10") (pin "2") (pinfunction "2_2") (pintype "passive"))
      (node (ref "R12") (pin "2") (pinfunction "2_2") (pintype "passive"))
      (node (ref "R17") (pin "2") (pinfunction "2_2") (pintype "passive"))
      (node (ref "R5") (pin "2") (pinfunction "2_2") (pintype "passive"))
    )
    (net (code "7") (name "/A") (class "Default")
      (node (ref "J14") (pin "4") (pinfunction "4_4") (pintype "passive"))
      (node (ref "J17") (pin "5") (pinfunction "5_5") (pintype "passive"))
      (node (ref "J18") (pin "1") (pinfunction "1_1") (pintype "passive"))
      (node (ref "R38") (pin "1") (pinfunction "1_1") (pintype "passive"))
    )
    (net (code "8") (name "/B") (class "Default")
      (node (ref "J14") (pin "3") (pinfunction "3_3") (pintype "passive"))
      (node (ref "J17") (pin "6") (pinfunction "6_6") (pintype "passive"))
      (node (ref "J25") (pin "1") (pinfunction "1_1") (pintype "passive"))
      (node (ref "R48") (pin "1") (pinfunction "1_1") (pintype "passive"))
    )
    (net (code "9") (name "/C") (class "Default")
      (node (ref "J14") (pin "2") (pinfunction "2_2") (pintype "passive"))
      (node (ref "J17") (pin "7") (pinfunction "7_7") (pintype "passive"))
      (node (ref "J32") (pin "1") (pinfunction "1_1") (pintype "passive"))
      (node (ref "R61") (pin "1") (pinfunction "1_1") (pintype "passive"))
    )
    (net (code "10") (name "/CTL_AD") (class "Default")
      (node (ref "C21") (pin "1") (pinfunction "1_1") (pintype "passive"))
      (node (ref "JP1") (pin "9") (pinfunction "9_9") (pintype "passive"))
      (node (ref "R30") (pin "2") (pinfunction "2_2") (pintype "passive"))
    )
    (net (code "11") (name "/CTL_PWM") (class "Default")
      (node (ref "JP2") (pin "14") (pinfunction "14_14") (pintype "passive"))
      (node (ref "R32") (pin "2") (pinfunction "2_2") (pintype "passive"))
    )
    (net (code "12") (name "/HALL_A") (class "Default")
      (node (ref "JP1") (pin "6") (pinfunction "6_6") (pintype "passive"))
      (node (ref "R37") (pin "1") (pinfunction "1_1") (pintype "passive"))
    )
    (net (code "13") (name "/HALL_B") (class "Default")
      (node (ref "JP1") (pin "4") (pinfunction "4_4") (pintype "passive"))
      (node (ref "R47") (pin "1") (pinfunction "1_1") (pintype "passive"))
    )
    (net (code "14") (name "/HALL_C") (class "Default")
      (node (ref "JP1") (pin "2") (pinfunction "2_2") (pintype "passive"))
      (node (ref "R60") (pin "1") (pinfunction "1_1") (pintype "passive"))
    )
    (net (code "15") (name "/KEY1") (class "Default")
      (node (ref "C43") (pin "1") (pinfunction "1_1") (pintype "passive"))
      (node (ref "JP1") (pin "16") (pinfunction "16_16") (pintype "passive"))
      (node (ref "R58") (pin "2") (pinfunction "2_2") (pintype "passive"))
    )
    (net (code "16") (name "/KEY2") (class "Default")
      (node (ref "C44") (pin "1") (pinfunction "1_1") (pintype "passive"))
      (node (ref "JP1") (pin "15") (pinfunction "15_15") (pintype "passive"))
      (node (ref "R59") (pin "2") (pinfunction "2_2") (pintype "passive"))
    )
    (net (code "17") (name "/KEY3") (class "Default")
      (node (ref "C45") (pin "1") (pinfunction "1_1") (pintype "passive"))
      (node (ref "JP1") (pin "18") (pinfunction "18_18") (pintype "passive"))
      (node (ref "R105") (pin "2") (pinfunction "2_2") (pintype "passive"))
    )
    (net (code "18") (name "/KEY4") (class "Default")
      (node (ref "C46") (pin "1") (pinfunction "1_1") (pintype "passive"))
      (node (ref "JP1") (pin "17") (pinfunction "17_17") (pintype "passive"))
      (node (ref "R106") (pin "2") (pinfunction "2_2") (pintype "passive"))
    )
    (net (code "19") (name "/SPI_CLK") (class "Default")
      (node (ref "J9") (pin "3") (pinfunction "3_3") (pintype "passive"))
      (node (ref "JP1") (pin "7") (pinfunction "7_7") (pintype "passive"))
    )
    (net (code "20") (name "/SPI_MISO") (class "Default")
      (node (ref "J9") (pin "5") (pinfunction "5_5") (pintype "passive"))
      (node (ref "JP1") (pin "3") (pinfunction "3_3") (pintype "passive"))
    )
    (net (code "21") (name "/SPI_MOSI") (class "Default")
      (node (ref "J9") (pin "4") (pinfunction "4_4") (pintype "passive"))
      (node (ref "JP1") (pin "5") (pinfunction "5_5") (pintype "passive"))
    )
    (net (code "22") (name "/SPI_NSS") (class "Default")
      (node (ref "J9") (pin "6") (pinfunction "6_6") (pintype "passive"))
      (node (ref "JP1") (pin "1") (pinfunction "1_1") (pintype "passive"))
    )
    (net (code "23") (name "/U+") (class "Default")
      (node (ref "JP2") (pin "6") (pinfunction "6_6") (pintype "passive"))
      (node (ref "R67") (pin "1") (pinfunction "1_1") (pintype "passive"))
    )
    (net (code "24") (name "/U-") (class "Default")
      (node (ref "JP2") (pin "12") (pinfunction "12_12") (pintype "passive"))
      (node (ref "R62") (pin "1") (pinfunction "1_1") (pintype "passive"))
    )
    (net (code "25") (name "/USART1_RX") (class "Default")
      (node (ref "J9") (pin "8") (pinfunction "8_8") (pintype "passive"))
      (node (ref "JP1") (pin "10") (pinfunction "10_10") (pintype "passive"))
      (node (ref "R22") (pin "1") (pinfunction "1_1") (pintype "passive"))
    )
    (net (code "26") (name "/USART1_TX") (class "Default")
      (node (ref "J9") (pin "7") (pinfunction "7_7") (pintype "passive"))
      (node (ref "JP1") (pin "8") (pinfunction "8_8") (pintype "passive"))
      (node (ref "R23") (pin "1") (pinfunction "1_1") (pintype "passive"))
    )
    (net (code "27") (name "/USART2_RX") (class "Default")
      (node (ref "JP2") (pin "16") (pinfunction "16_16") (pintype "passive"))
      (node (ref "R31") (pin "2") (pinfunction "2_2") (pintype "passive"))
    )
    (net (code "28") (name "/USART2_TX") (class "Default")
      (node (ref "JP2") (pin "18") (pinfunction "18_18") (pintype "passive"))
      (node (ref "R29") (pin "2") (pinfunction "2_2") (pintype "passive"))
    )
    (net (code "29") (name "/UU") (class "Default")
      (node (ref "C23") (pin "2") (pinfunction "2_2") (pintype "passive"))
      (node (ref "JP3") (pin "4") (pinfunction "4_4") (pintype "passive"))
      (node (ref "U4") (pin "12") (pinfunction "VS3_12") (pintype "passive"))
    )
    (net (code "30") (name "/U_H") (class "Default")
      (node (ref "JP3") (pin "5") (pinfunction "5_5") (pintype "passive"))
      (node (ref "R39") (pin "1") (pinfunction "1_1") (pintype "passive"))
    )
    (net (code "31") (name "/U_IN_H") (class "Default")
      (node (ref "JP4") (pin "13") (pinfunction "13_13") (pintype "passive"))
      (node (ref "U4") (pin "3") (pinfunction "HIN3_3") (pintype "passive"))
    )
    (net (code "32") (name "/U_IN_L") (class "Default")
      (node (ref "JP4") (pin "7") (pinfunction "7_7") (pintype "passive"))
      (node (ref "U4") (pin "6") (pinfunction "LIN3_6") (pintype "passive"))
    )
    (net (code "33") (name "/U_L") (class "Default")
      (node (ref "JP3") (pin "1") (pinfunction "1_1") (pintype "passive"))
      (node (ref "R51") (pin "2") (pinfunction "2_2") (pintype "passive"))
    )
    (net (code "34") (name "/U_OUT_H") (class "Default")
      (node (ref "JP3") (pin "6") (pinfunction "6_6") (pintype "passive"))
      (node (ref "U4") (pin "13") (pinfunction "HO3_13") (pintype "passive"))
    )
    (net (code "35") (name "/U_OUT_L") (class "Default")
      (node (ref "JP3") (pin "2") (pinfunction "2_2") (pintype "passive"))
      (node (ref "U4") (pin "9") (pinfunction "LO3_9") (pintype "passive"))
    )
    (net (code "36") (name "/V+") (class "Default")
      (node (ref "JP2") (pin "4") (pinfunction "4_4") (pintype "passive"))
      (node (ref "R68") (pin "1") (pinfunction "1_1") (pintype "passive"))
    )
    (net (code "37") (name "/V-") (class "Default")
      (node (ref "JP2") (pin "10") (pinfunction "10_10") (pintype "passive"))
      (node (ref "R63") (pin "1") (pinfunction "1_1") (pintype "passive"))
    )
    (net (code "38") (name "/VIN_AD") (class "Default")
      (node (ref "C19") (pin "1") (pinfunction "1_1") (pintype "passive"))
      (node (ref "JP2") (pin "1") (pinfunction "1_1") (pintype "passive"))
      (node (ref "R28") (pin "2") (pinfunction "2_2") (pintype "passive"))
      (node (ref "R33") (pin "1") (pinfunction "1_1") (pintype "passive"))
    )
    (net (code "39") (name "/VV") (class "Default")
      (node (ref "C27") (pin "2") (pinfunction "2_2") (pintype "passive"))
      (node (ref "JP3") (pin "10") (pinfunction "10_10") (pintype "passive"))
      (node (ref "U4") (pin "15") (pinfunction "VS2_15") (pintype "passive"))
    )
    (net (code "40") (name "/V_H") (class "Default")
      (node (ref "JP3") (pin "11") (pinfunction "11_11") (pintype "passive"))
      (node (ref "R40") (pin "1") (pinfunction "1_1") (pintype "passive"))
    )
    (net (code "41") (name "/V_IN_H") (class "Default")
      (node (ref "JP4") (pin "15") (pinfunction "15_15") (pintype "passive"))
      (node (ref "U4") (pin "2") (pinfunction "HIN2_2") (pintype "passive"))
    )
    (net (code "42") (name "/V_IN_L") (class "Default")
      (node (ref "JP4") (pin "9") (pinfunction "9_9") (pintype "passive"))
      (node (ref "U4") (pin "5") (pinfunction "LIN2_5") (pintype "passive"))
    )
    (net (code "43") (name "/V_L") (class "Default")
      (node (ref "JP3") (pin "7") (pinfunction "7_7") (pintype "passive"))
      (node (ref "R52") (pin "2") (pinfunction "2_2") (pintype "passive"))
    )
    (net (code "44") (name "/V_OUT_H") (class "Default")
      (node (ref "JP3") (pin "12") (pinfunction "12_12") (pintype "passive"))
      (node (ref "U4") (pin "16") (pinfunction "HO2_16") (pintype "passive"))
    )
    (net (code "45") (name "/V_OUT_L") (class "Default")
      (node (ref "JP3") (pin "8") (pinfunction "8_8") (pintype "passive"))
      (node (ref "U4") (pin "10") (pinfunction "LO2_10") (pintype "passive"))
    )
    (net (code "46") (name "/W+") (class "Default")
      (node (ref "JP2") (pin "2") (pinfunction "2_2") (pintype "passive"))
      (node (ref "R69") (pin "1") (pinfunction "1_1") (pintype "passive"))
    )
    (net (code "47") (name "/W-") (class "Default")
      (node (ref "JP2") (pin "8") (pinfunction "8_8") (pintype "passive"))
      (node (ref "R66") (pin "1") (pinfunction "1_1") (pintype "passive"))
    )
    (net (code "48") (name "/WW") (class "Default")
      (node (ref "C32") (pin "2") (pinfunction "2_2") (pintype "passive"))
      (node (ref "JP3") (pin "16") (pinfunction "16_16") (pintype "passive"))
      (node (ref "U4") (pin "18") (pinfunction "VS1_18") (pintype "passive"))
    )
    (net (code "49") (name "/W_H") (class "Default")
      (node (ref "JP3") (pin "17") (pinfunction "17_17") (pintype "passive"))
      (node (ref "R41") (pin "1") (pinfunction "1_1") (pintype "passive"))
    )
    (net (code "50") (name "/W_IN_H") (class "Default")
      (node (ref "JP4") (pin "17") (pinfunction "17_17") (pintype "passive"))
      (node (ref "U4") (pin "1") (pinfunction "HIN1_1") (pintype "passive"))
    )
    (net (code "51") (name "/W_IN_L") (class "Default")
      (node (ref "JP4") (pin "11") (pinfunction "11_11") (pintype "passive"))
      (node (ref "U4") (pin "4") (pinfunction "LIN1_4") (pintype "passive"))
    )
    (net (code "52") (name "/W_L") (class "Default")
      (node (ref "JP3") (pin "13") (pinfunction "13_13") (pintype "passive"))
      (node (ref "R53") (pin "2") (pinfunction "2_2") (pintype "passive"))
    )
    (net (code "53") (name "/W_OUT_H") (class "Default")
      (node (ref "JP3") (pin "18") (pinfunction "18_18") (pintype "passive"))
      (node (ref "U4") (pin "19") (pinfunction "HO1_19") (pintype "passive"))
    )
    (net (code "54") (name "/W_OUT_L") (class "Default")
      (node (ref "JP3") (pin "14") (pinfunction "14_14") (pintype "passive"))
      (node (ref "U4") (pin "11") (pinfunction "LO1_11") (pintype "passive"))
    )
    (net (code "55") (name "BUS_CURR") (class "Default")
      (node (ref "J38") (pin "1") (pinfunction "1_1") (pintype "passive"))
      (node (ref "JP1") (pin "13") (pinfunction "13_13") (pintype "passive"))
      (node (ref "R84") (pin "1") (pinfunction "1_1") (pintype "passive"))
    )
    (net (code "56") (name "BUS_I+") (class "Default")
      (node (ref "R112") (pin "2") (pinfunction "2_2") (pintype "passive"))
      (node (ref "R34") (pin "2") (pinfunction "2_2") (pintype "passive"))
      (node (ref "R49") (pin "1") (pinfunction "1_1") (pintype "passive"))
    )
    (net (code "57") (name "BUS_I-") (class "Default")
      (node (ref "R108") (pin "2") (pinfunction "2_2") (pintype "passive"))
      (node (ref "R35") (pin "2") (pinfunction "2_2") (pintype "passive"))
      (node (ref "R50") (pin "1") (pinfunction "1_1") (pintype "passive"))
    )
    (net (code "58") (name "FD_12V") (class "Default")
      (node (ref "C26") (pin "1") (pinfunction "1_1") (pintype "passive"))
      (node (ref "D5") (pin "1") (pinfunction "1_1") (pintype "passive"))
      (node (ref "D6") (pin "1") (pinfunction "1_1") (pintype "passive"))
      (node (ref "D7") (pin "1") (pinfunction "1_1") (pintype "passive"))
      (node (ref "R42") (pin "2") (pinfunction "2_2") (pintype "passive"))
      (node (ref "U4") (pin "7") (pinfunction "VCC_7") (pintype "passive"))
    )
    (net (code "59") (name "GND") (class "Default")
      (node (ref "C10") (pin "2") (pinfunction "2_2") (pintype "passive"))
      (node (ref "C11") (pin "2") (pinfunction "2_2") (pintype "passive"))
      (node (ref "C12") (pin "2") (pinfunction "2_2") (pintype "passive"))
      (node (ref "C13") (pin "2") (pinfunction "2_2") (pintype "passive"))
      (node (ref "C14") (pin "2") (pinfunction "2_2") (pintype "passive"))
      (node (ref "C15") (pin "2") (pinfunction "2_2") (pintype "passive"))
      (node (ref "C18") (pin "2") (pinfunction "2_2") (pintype "passive"))
      (node (ref "C19") (pin "2") (pinfunction "2_2") (pintype "passive"))
      (node (ref "C20") (pin "2") (pinfunction "2_2") (pintype "passive"))
      (node (ref "C21") (pin "2") (pinfunction "2_2") (pintype "passive"))
      (node (ref "C24") (pin "2") (pinfunction "2_2") (pintype "passive"))
      (node (ref "C25") (pin "2") (pinfunction "2_2") (pintype "passive"))
      (node (ref "C31") (pin "2") (pinfunction "2_2") (pintype "passive"))
      (node (ref "C33") (pin "2") (pinfunction "2_2") (pintype "passive"))
      (node (ref "C4") (pin "2") (pinfunction "2_2") (pintype "passive"))
      (node (ref "C42") (pin "1") (pinfunction "1_1") (pintype "passive"))
      (node (ref "C43") (pin "2") (pinfunction "2_2") (pintype "passive"))
      (node (ref "C44") (pin "2") (pinfunction "2_2") (pintype "passive"))
      (node (ref "C45") (pin "2") (pinfunction "2_2") (pintype "passive"))
      (node (ref "C46") (pin "2") (pinfunction "2_2") (pintype "passive"))
      (node (ref "C5") (pin "2") (pinfunction "2_2") (pintype "passive"))
      (node (ref "C6") (pin "2") (pinfunction "2_2") (pintype "passive"))
      (node (ref "C7") (pin "2") (pinfunction "2_2") (pintype "passive"))
      (node (ref "C8") (pin "2") (pinfunction "2_2") (pintype "passive"))
      (node (ref "C9") (pin "2") (pinfunction "2_2") (pintype "passive"))
      (node (ref "D3") (pin "1") (pinfunction "1_1") (pintype "passive"))
      (node (ref "J13") (pin "4") (pinfunction "4_4") (pintype "passive"))
      (node (ref "J14") (pin "5") (pinfunction "5_5") (pintype "passive"))
      (node (ref "J17") (pin "4") (pinfunction "4_4") (pintype "passive"))
      (node (ref "J3") (pin "2") (pinfunction "2_2") (pintype "passive"))
      (node (ref "J36") (pin "1") (pinfunction "1_1") (pintype "passive"))
      (node (ref "J4") (pin "2") (pinfunction "2_2") (pintype "passive"))
      (node (ref "J8") (pin "1") (pinfunction "1_1") (pintype "passive"))
      (node (ref "J9") (pin "1") (pinfunction "1_1") (pintype "passive"))
      (node (ref "JP2") (pin "11") (pinfunction "11_11") (pintype "passive"))
      (node (ref "JP2") (pin "13") (pinfunction "13_13") (pintype "passive"))
      (node (ref "JP4") (pin "4") (pinfunction "4_4") (pintype "passive"))
      (node (ref "Q2") (pin "2") (pinfunction "E_2") (pintype "passive"))
      (node (ref "R102") (pin "2") (pinfunction "2_2") (pintype "passive"))
      (node (ref "R103") (pin "2") (pinfunction "2_2") (pintype "passive"))
      (node (ref "R104") (pin "2") (pinfunction "2_2") (pintype "passive"))
      (node (ref "R111") (pin "2") (pinfunction "2_2") (pintype "passive"))
      (node (ref "R15") (pin "2") (pinfunction "2_2") (pintype "passive"))
      (node (ref "R16") (pin "2") (pinfunction "2_2") (pintype "passive"))
      (node (ref "R17") (pin "1") (pinfunction "1_1") (pintype "passive"))
      (node (ref "R19") (pin "1") (pinfunction "1_1") (pintype "passive"))
      (node (ref "R20") (pin "2") (pinfunction "2_2") (pintype "passive"))
      (node (ref "R21") (pin "2") (pinfunction "2_2") (pintype "passive"))
      (node (ref "R23") (pin "2") (pinfunction "2_2") (pintype "passive"))
      (node (ref "R30") (pin "1") (pinfunction "1_1") (pintype "passive"))
      (node (ref "R33") (pin "2") (pinfunction "2_2") (pintype "passive"))
      (node (ref "R34") (pin "1") (pinfunction "1_1") (pintype "passive"))
      (node (ref "R35") (pin "1") (pinfunction "1_1") (pintype "passive"))
      (node (ref "R70") (pin "2") (pinfunction "2_2") (pintype "passive"))
      (node (ref "R8") (pin "2") (pinfunction "2_2") (pintype "passive"))
      (node (ref "R9") (pin "1") (pinfunction "1_1") (pintype "passive"))
      (node (ref "R93") (pin "2") (pinfunction "2_2") (pintype "passive"))
      (node (ref "R96") (pin "2") (pinfunction "2_2") (pintype "passive"))
      (node (ref "R97") (pin "1") (pinfunction "1_1") (pintype "passive"))
      (node (ref "R98") (pin "1") (pinfunction "1_1") (pintype "passive"))
      (node (ref "R99") (pin "1") (pinfunction "1_1") (pintype "passive"))
      (node (ref "SW1") (pin "1") (pinfunction "1_1") (pintype "passive"))
      (node (ref "SW2") (pin "1") (pinfunction "1_1") (pintype "passive"))
      (node (ref "SW3") (pin "1") (pinfunction "1_1") (pintype "passive"))
      (node (ref "SW4") (pin "1") (pinfunction "1_1") (pintype "passive"))
      (node (ref "U1") (pin "4") (pinfunction "GND_4") (pintype "passive"))
      (node (ref "U2") (pin "2") (pinfunction "GND_2") (pintype "passive"))
      (node (ref "U3") (pin "1") (pinfunction "GND_1") (pintype "passive"))
      (node (ref "U5") (pin "11") (pinfunction "VS-_11") (pintype "passive"))
    )
    (net (code "60") (name "GND-1") (class "Default")
      (node (ref "C26") (pin "2") (pinfunction "2_2") (pintype "passive"))
      (node (ref "JP4") (pin "3") (pinfunction "3_3") (pintype "passive"))
      (node (ref "U4") (pin "8") (pinfunction "COM_8") (pintype "passive"))
    )
    (net (code "61") (name "Net-(C1-Pad2)") (class "Default")
      (node (ref "C1") (pin "2") (pinfunction "2_2") (pintype "passive"))
      (node (ref "R1") (pin "1") (pinfunction "1_1") (pintype "passive"))
    )
    (net (code "62") (name "Net-(C2-Pad1)") (class "Default")
      (node (ref "C2") (pin "1") (pinfunction "1_1") (pintype "passive"))
      (node (ref "R3") (pin "2") (pinfunction "2_2") (pintype "passive"))
    )
    (net (code "63") (name "Net-(C16-Pad2)") (class "Default")
      (node (ref "C16") (pin "2") (pinfunction "2_2") (pintype "passive"))
      (node (ref "R16") (pin "1") (pinfunction "1_1") (pintype "passive"))
    )
    (net (code "64") (name "Net-(C17-Pad1)") (class "Default")
      (node (ref "C17") (pin "1") (pinfunction "1_1") (pintype "passive"))
      (node (ref "R19") (pin "2") (pinfunction "2_2") (pintype "passive"))
    )
    (net (code "65") (name "Net-(C24-Pad1)") (class "Default")
      (node (ref "C24") (pin "1") (pinfunction "1_1") (pintype "passive"))
      (node (ref "R36") (pin "1") (pinfunction "1_1") (pintype "passive"))
      (node (ref "R37") (pin "2") (pinfunction "2_2") (pintype "passive"))
      (node (ref "R38") (pin "2") (pinfunction "2_2") (pintype "passive"))
    )
    (net (code "66") (name "Net-(C31-Pad1)") (class "Default")
      (node (ref "C31") (pin "1") (pinfunction "1_1") (pintype "passive"))
      (node (ref "R46") (pin "1") (pinfunction "1_1") (pintype "passive"))
      (node (ref "R47") (pin "2") (pinfunction "2_2") (pintype "passive"))
      (node (ref "R48") (pin "2") (pinfunction "2_2") (pintype "passive"))
    )
    (net (code "67") (name "Net-(C33-Pad1)") (class "Default")
      (node (ref "C33") (pin "1") (pinfunction "1_1") (pintype "passive"))
      (node (ref "R57") (pin "1") (pinfunction "1_1") (pintype "passive"))
      (node (ref "R60") (pin "2") (pinfunction "2_2") (pintype "passive"))
      (node (ref "R61") (pin "2") (pinfunction "2_2") (pintype "passive"))
    )
    (net (code "68") (name "Net-(C34-Pad1)") (class "Default")
      (node (ref "C34") (pin "1") (pinfunction "1_1") (pintype "passive"))
      (node (ref "R108") (pin "1") (pinfunction "1_1") (pintype "passive"))
      (node (ref "R74") (pin "2") (pinfunction "2_2") (pintype "passive"))
    )
    (net (code "69") (name "Net-(C34-Pad2)") (class "Default")
      (node (ref "C34") (pin "2") (pinfunction "2_2") (pintype "passive"))
      (node (ref "R112") (pin "1") (pinfunction "1_1") (pintype "passive"))
      (node (ref "R88") (pin "2") (pinfunction "2_2") (pintype "passive"))
    )
    (net (code "70") (name "Net-(C35-Pad1)") (class "Default")
      (node (ref "C35") (pin "1") (pinfunction "1_1") (pintype "passive"))
      (node (ref "R109") (pin "1") (pinfunction "1_1") (pintype "passive"))
      (node (ref "R76") (pin "2") (pinfunction "2_2") (pintype "passive"))
    )
    (net (code "71") (name "Net-(C35-Pad2)") (class "Default")
      (node (ref "C35") (pin "2") (pinfunction "2_2") (pintype "passive"))
      (node (ref "R113") (pin "1") (pinfunction "1_1") (pintype "passive"))
      (node (ref "R89") (pin "2") (pinfunction "2_2") (pintype "passive"))
    )
    (net (code "72") (name "Net-(C36-Pad1)") (class "Default")
      (node (ref "C36") (pin "1") (pinfunction "1_1") (pintype "passive"))
      (node (ref "R110") (pin "1") (pinfunction "1_1") (pintype "passive"))
      (node (ref "R78") (pin "2") (pinfunction "2_2") (pintype "passive"))
    )
    (net (code "73") (name "Net-(C36-Pad2)") (class "Default")
      (node (ref "C36") (pin "2") (pinfunction "2_2") (pintype "passive"))
      (node (ref "R114") (pin "1") (pinfunction "1_1") (pintype "passive"))
      (node (ref "R90") (pin "2") (pinfunction "2_2") (pintype "passive"))
    )
    (net (code "74") (name "Net-(C37-Pad1)") (class "Default")
      (node (ref "C37") (pin "1") (pinfunction "1_1") (pintype "passive"))
      (node (ref "R111") (pin "1") (pinfunction "1_1") (pintype "passive"))
      (node (ref "R80") (pin "2") (pinfunction "2_2") (pintype "passive"))
    )
    (net (code "75") (name "Net-(C37-Pad2)") (class "Default")
      (node (ref "C37") (pin "2") (pinfunction "2_2") (pintype "passive"))
      (node (ref "R115") (pin "1") (pinfunction "1_1") (pintype "passive"))
      (node (ref "R91") (pin "2") (pinfunction "2_2") (pintype "passive"))
    )
    (net (code "76") (name "Net-(D4-A)") (class "Default")
      (node (ref "D4") (pin "1") (pinfunction "A_1") (pintype "passive"))
      (node (ref "Q2") (pin "1") (pinfunction "B_1") (pintype "passive"))
      (node (ref "R20") (pin "1") (pinfunction "1_1") (pintype "passive"))
    )
    (net (code "77") (name "Net-(D4-K)") (class "Default")
      (node (ref "D4") (pin "2") (pinfunction "K_2") (pintype "passive"))
      (node (ref "R18") (pin "1") (pinfunction "1_1") (pintype "passive"))
    )
    (net (code "78") (name "Net-(D8-Pad2)") (class "Default")
      (node (ref "D8") (pin "2") (pinfunction "2_2") (pintype "passive"))
      (node (ref "R104") (pin "1") (pinfunction "1_1") (pintype "passive"))
    )
    (net (code "79") (name "Net-(J13-Pad1)") (class "Default")
      (node (ref "J13") (pin "1") (pinfunction "1_1") (pintype "passive"))
      (node (ref "R29") (pin "1") (pinfunction "1_1") (pintype "passive"))
    )
    (net (code "80") (name "Net-(J13-Pad2)") (class "Default")
      (node (ref "J13") (pin "2") (pinfunction "2_2") (pintype "passive"))
      (node (ref "R31") (pin "1") (pinfunction "1_1") (pintype "passive"))
    )
    (net (code "81") (name "Net-(J13-Pad3)") (class "Default")
      (node (ref "J13") (pin "3") (pinfunction "3_3") (pintype "passive"))
      (node (ref "R32") (pin "1") (pinfunction "1_1") (pintype "passive"))
    )
    (net (code "82") (name "Net-(JP4-Pad8)") (class "Default")
      (node (ref "JP4") (pin "8") (pinfunction "8_8") (pintype "passive"))
      (node (ref "R62") (pin "2") (pinfunction "2_2") (pintype "passive"))
    )
    (net (code "83") (name "Net-(JP4-Pad10)") (class "Default")
      (node (ref "JP4") (pin "10") (pinfunction "10_10") (pintype "passive"))
      (node (ref "R63") (pin "2") (pinfunction "2_2") (pintype "passive"))
    )
    (net (code "84") (name "Net-(JP4-Pad12)") (class "Default")
      (node (ref "JP4") (pin "12") (pinfunction "12_12") (pintype "passive"))
      (node (ref "R66") (pin "2") (pinfunction "2_2") (pintype "passive"))
    )
    (net (code "85") (name "Net-(JP4-Pad14)") (class "Default")
      (node (ref "JP4") (pin "14") (pinfunction "14_14") (pintype "passive"))
      (node (ref "R67") (pin "2") (pinfunction "2_2") (pintype "passive"))
    )
    (net (code "86") (name "Net-(JP4-Pad16)") (class "Default")
      (node (ref "JP4") (pin "16") (pinfunction "16_16") (pintype "passive"))
      (node (ref "R68") (pin "2") (pinfunction "2_2") (pintype "passive"))
    )
    (net (code "87") (name "Net-(JP4-Pad18)") (class "Default")
      (node (ref "JP4") (pin "18") (pinfunction "18_18") (pintype "passive"))
      (node (ref "R69") (pin "2") (pinfunction "2_2") (pintype "passive"))
    )
    (net (code "88") (name "Net-(M1-GATE)") (class "Default")
      (node (ref "J19") (pin "1") (pinfunction "1_1") (pintype "passive"))
      (node (ref "M1") (pin "1") (pinfunction "GATE_1") (pintype "input"))
      (node (ref "R39") (pin "2") (pinfunction "2_2") (pintype "passive"))
      (node (ref "R43") (pin "1") (pinfunction "1_1") (pintype "passive"))
    )
    (net (code "89") (name "Net-(M2-GATE)") (class "Default")
      (node (ref "J20") (pin "1") (pinfunction "1_1") (pintype "passive"))
      (node (ref "M2") (pin "1") (pinfunction "GATE_1") (pintype "input"))
      (node (ref "R40") (pin "2") (pinfunction "2_2") (pintype "passive"))
      (node (ref "R44") (pin "1") (pinfunction "1_1") (pintype "passive"))
    )
    (net (code "90") (name "Net-(M3-GATE)") (class "Default")
      (node (ref "J21") (pin "1") (pinfunction "1_1") (pintype "passive"))
      (node (ref "M3") (pin "1") (pinfunction "GATE_1") (pintype "input"))
      (node (ref "R41") (pin "2") (pinfunction "2_2") (pintype "passive"))
      (node (ref "R45") (pin "1") (pinfunction "1_1") (pintype "passive"))
    )
    (net (code "91") (name "Net-(M4-GATE)") (class "Default")
      (node (ref "J27") (pin "1") (pinfunction "1_1") (pintype "passive"))
      (node (ref "M4") (pin "1") (pinfunction "GATE_1") (pintype "input"))
      (node (ref "R51") (pin "1") (pinfunction "1_1") (pintype "passive"))
      (node (ref "R54") (pin "2") (pinfunction "2_2") (pintype "passive"))
    )
    (net (code "92") (name "Net-(M5-GATE)") (class "Default")
      (node (ref "J28") (pin "1") (pinfunction "1_1") (pintype "passive"))
      (node (ref "M5") (pin "1") (pinfunction "GATE_1") (pintype "input"))
      (node (ref "R52") (pin "1") (pinfunction "1_1") (pintype "passive"))
      (node (ref "R55") (pin "2") (pinfunction "2_2") (pintype "passive"))
    )
    (net (code "93") (name "Net-(M6-GATE)") (class "Default")
      (node (ref "J29") (pin "1") (pinfunction "1_1") (pintype "passive"))
      (node (ref "M6") (pin "1") (pinfunction "GATE_1") (pintype "input"))
      (node (ref "R53") (pin "1") (pinfunction "1_1") (pintype "passive"))
      (node (ref "R56") (pin "2") (pinfunction "2_2") (pintype "passive"))
    )
    (net (code "94") (name "Net-(Q1-D)") (class "Default")
      (node (ref "D2") (pin "2") (pinfunction "2_2") (pintype "passive"))
      (node (ref "J1") (pin "1") (pinfunction "1_1") (pintype "passive"))
      (node (ref "Q1") (pin "2") (pinfunction "D_2") (pintype "passive"))
      (node (ref "R1") (pin "2") (pinfunction "2_2") (pintype "passive"))
      (node (ref "R2") (pin "1") (pinfunction "1_1") (pintype "passive"))
      (node (ref "R49") (pin "2") (pinfunction "2_2") (pintype "passive"))
    )
    (net (code "95") (name "Net-(Q1-G)") (class "Default")
      (node (ref "C3") (pin "1") (pinfunction "1_1") (pintype "passive"))
      (node (ref "Q1") (pin "1") (pinfunction "G_1") (pintype "passive"))
      (node (ref "R13") (pin "1") (pinfunction "1_1") (pintype "passive"))
      (node (ref "R5") (pin "1") (pinfunction "1_1") (pintype "passive"))
    )
    (net (code "96") (name "Net-(Q2-C)") (class "Default")
      (node (ref "Q2") (pin "3") (pinfunction "C_3") (pintype "passive"))
      (node (ref "R13") (pin "2") (pinfunction "2_2") (pintype "passive"))
    )
    (net (code "97") (name "Net-(R24-Pad2)") (class "Default")
      (node (ref "R24") (pin "2") (pinfunction "2_2") (pintype "passive"))
      (node (ref "R58") (pin "1") (pinfunction "1_1") (pintype "passive"))
      (node (ref "SW1") (pin "2") (pinfunction "2_2") (pintype "passive"))
    )
    (net (code "98") (name "Net-(R25-Pad2)") (class "Default")
      (node (ref "R25") (pin "2") (pinfunction "2_2") (pintype "passive"))
      (node (ref "R59") (pin "1") (pinfunction "1_1") (pintype "passive"))
      (node (ref "SW2") (pin "2") (pinfunction "2_2") (pintype "passive"))
    )
    (net (code "99") (name "Net-(R100-Pad1)") (class "Default")
      (node (ref "R100") (pin "1") (pinfunction "1_1") (pintype "passive"))
      (node (ref "R102") (pin "1") (pinfunction "1_1") (pintype "passive"))
      (node (ref "R94") (pin "2") (pinfunction "2_2") (pintype "passive"))
    )
    (net (code "100") (name "Net-(R101-Pad1)") (class "Default")
      (node (ref "R101") (pin "1") (pinfunction "1_1") (pintype "passive"))
      (node (ref "R103") (pin "1") (pinfunction "1_1") (pintype "passive"))
      (node (ref "R95") (pin "2") (pinfunction "2_2") (pintype "passive"))
    )
    (net (code "101") (name "Net-(R105-Pad1)") (class "Default")
      (node (ref "R105") (pin "1") (pinfunction "1_1") (pintype "passive"))
      (node (ref "R26") (pin "2") (pinfunction "2_2") (pintype "passive"))
      (node (ref "SW3") (pin "2") (pinfunction "2_2") (pintype "passive"))
    )
    (net (code "102") (name "Net-(R106-Pad1)") (class "Default")
      (node (ref "R106") (pin "1") (pinfunction "1_1") (pintype "passive"))
      (node (ref "R27") (pin "2") (pinfunction "2_2") (pintype "passive"))
      (node (ref "SW4") (pin "2") (pinfunction "2_2") (pintype "passive"))
    )
    (net (code "103") (name "Net-(S1-COMMON)") (class "Default")
      (node (ref "R10") (pin "1") (pinfunction "1_1") (pintype "passive"))
      (node (ref "R12") (pin "1") (pinfunction "1_1") (pintype "passive"))
      (node (ref "S1") (pin "1") (pinfunction "COMMON_1") (pintype "passive"))
    )
    (net (code "104") (name "Net-(S1-NO)") (class "Default")
      (node (ref "C18") (pin "1") (pinfunction "1_1") (pintype "passive"))
      (node (ref "D2") (pin "1") (pinfunction "1_1") (pintype "passive"))
      (node (ref "R18") (pin "2") (pinfunction "2_2") (pintype "passive"))
      (node (ref "R21") (pin "1") (pinfunction "1_1") (pintype "passive"))
      (node (ref "S1") (pin "2") (pinfunction "NO_2") (pintype "passive"))
    )
    (net (code "105") (name "Net-(U1-BS)") (class "Default")
      (node (ref "R3") (pin "1") (pinfunction "1_1") (pintype "passive"))
      (node (ref "U1") (pin "1") (pinfunction "BS_1") (pintype "passive"))
    )
    (net (code "106") (name "Net-(U1-COMP)") (class "Default")
      (node (ref "C16") (pin "1") (pinfunction "1_1") (pintype "passive"))
      (node (ref "U1") (pin "6") (pinfunction "COMP_6") (pintype "passive"))
    )
    (net (code "107") (name "Net-(U1-EN)") (class "Default")
      (node (ref "R4") (pin "2") (pinfunction "2_2") (pintype "passive"))
      (node (ref "R8") (pin "1") (pinfunction "1_1") (pintype "passive"))
      (node (ref "U1") (pin "7") (pinfunction "EN_7") (pintype "passive"))
    )
    (net (code "108") (name "Net-(U1-FB)") (class "Default")
      (node (ref "R11") (pin "2") (pinfunction "2_2") (pintype "passive"))
      (node (ref "R15") (pin "1") (pinfunction "1_1") (pintype "passive"))
      (node (ref "U1") (pin "5") (pinfunction "FB_5") (pintype "passive"))
    )
    (net (code "109") (name "Net-(U1-SS)") (class "Default")
      (node (ref "C15") (pin "1") (pinfunction "1_1") (pintype "passive"))
      (node (ref "U1") (pin "8") (pinfunction "SS_8") (pintype "passive"))
    )
    (net (code "110") (name "Net-(U1-SW)") (class "Default")
      (node (ref "C2") (pin "2") (pinfunction "2_2") (pintype "passive"))
      (node (ref "D3") (pin "2") (pinfunction "2_2") (pintype "passive"))
      (node (ref "L1") (pin "1") (pinfunction "1_1") (pintype "passive"))
      (node (ref "U1") (pin "3") (pinfunction "SW_3") (pintype "passive"))
    )
    (net (code "111") (name "Net-(U2-Vin)") (class "Default")
      (node (ref "C13") (pin "1") (pinfunction "1_1") (pintype "passive"))
      (node (ref "C14") (pin "1") (pinfunction "1_1") (pintype "passive"))
      (node (ref "R6") (pin "2") (pinfunction "2_2") (pintype "passive"))
      (node (ref "U2") (pin "1") (pinfunction "Vin_1") (pintype "passive"))
    )
    (net (code "112") (name "Net-(U4-VB1)") (class "Default")
      (node (ref "C32") (pin "1") (pinfunction "1_1") (pintype "passive"))
      (node (ref "D7") (pin "2") (pinfunction "1_2") (pintype "passive"))
      (node (ref "J35") (pin "1") (pinfunction "1_1") (pintype "passive"))
      (node (ref "U4") (pin "20") (pinfunction "VB1_20") (pintype "passive"))
    )
    (net (code "113") (name "Net-(U4-VB2)") (class "Default")
      (node (ref "C27") (pin "1") (pinfunction "1_1") (pintype "passive"))
      (node (ref "D6") (pin "2") (pinfunction "1_2") (pintype "passive"))
      (node (ref "J26") (pin "1") (pinfunction "1_1") (pintype "passive"))
      (node (ref "U4") (pin "17") (pinfunction "VB2_17") (pintype "passive"))
    )
    (net (code "114") (name "Net-(U4-VB3)") (class "Default")
      (node (ref "C23") (pin "1") (pinfunction "1_1") (pintype "passive"))
      (node (ref "D5") (pin "2") (pinfunction "1_2") (pintype "passive"))
      (node (ref "J16") (pin "1") (pinfunction "1_1") (pintype "passive"))
      (node (ref "U4") (pin "14") (pinfunction "VB3_14") (pintype "passive"))
    )
    (net (code "115") (name "Net-(U5A-A+)") (class "Default")
      (node (ref "R91") (pin "1") (pinfunction "1_1") (pintype "passive"))
      (node (ref "R96") (pin "1") (pinfunction "1_1") (pintype "passive"))
      (node (ref "U5") (pin "3") (pinfunction "A+_3") (pintype "passive"))
    )
    (net (code "116") (name "Net-(U5A-A-)") (class "Default")
      (node (ref "R80") (pin "1") (pinfunction "1_1") (pintype "passive"))
      (node (ref "R81") (pin "2") (pinfunction "2_2") (pintype "passive"))
      (node (ref "U5") (pin "2") (pinfunction "A-_2") (pintype "passive"))
    )
    (net (code "117") (name "Net-(U5A-A_O)") (class "Default")
      (node (ref "R81") (pin "1") (pinfunction "1_1") (pintype "passive"))
      (node (ref "R87") (pin "2") (pinfunction "2_2") (pintype "passive"))
      (node (ref "U5") (pin "1") (pinfunction "A_O_1") (pintype "passive"))
    )
    (net (code "118") (name "Net-(U5B-B+)") (class "Default")
      (node (ref "R88") (pin "1") (pinfunction "1_1") (pintype "passive"))
      (node (ref "R93") (pin "1") (pinfunction "1_1") (pintype "passive"))
      (node (ref "U5") (pin "5") (pinfunction "B+_5") (pintype "passive"))
    )
    (net (code "119") (name "Net-(U5B-B-)") (class "Default")
      (node (ref "R74") (pin "1") (pinfunction "1_1") (pintype "passive"))
      (node (ref "R75") (pin "2") (pinfunction "2_2") (pintype "passive"))
      (node (ref "U5") (pin "6") (pinfunction "B-_6") (pintype "passive"))
    )
    (net (code "120") (name "Net-(U5B-B_O)") (class "Default")
      (node (ref "R75") (pin "1") (pinfunction "1_1") (pintype "passive"))
      (node (ref "R84") (pin "2") (pinfunction "2_2") (pintype "passive"))
      (node (ref "U5") (pin "7") (pinfunction "B_O_7") (pintype "passive"))
    )
    (net (code "121") (name "Net-(U5C-C+)") (class "Default")
      (node (ref "R89") (pin "1") (pinfunction "1_1") (pintype "passive"))
      (node (ref "R94") (pin "1") (pinfunction "1_1") (pintype "passive"))
      (node (ref "U5") (pin "10") (pinfunction "C+_10") (pintype "passive"))
    )
    (net (code "122") (name "Net-(U5C-C-)") (class "Default")
      (node (ref "R76") (pin "1") (pinfunction "1_1") (pintype "passive"))
      (node (ref "R77") (pin "2") (pinfunction "2_2") (pintype "passive"))
      (node (ref "U5") (pin "9") (pinfunction "C-_9") (pintype "passive"))
    )
    (net (code "123") (name "Net-(U5C-C_O)") (class "Default")
      (node (ref "R77") (pin "1") (pinfunction "1_1") (pintype "passive"))
      (node (ref "R85") (pin "2") (pinfunction "2_2") (pintype "passive"))
      (node (ref "U5") (pin "8") (pinfunction "C_O_8") (pintype "passive"))
    )
    (net (code "124") (name "Net-(U5D-D+)") (class "Default")
      (node (ref "R90") (pin "1") (pinfunction "1_1") (pintype "passive"))
      (node (ref "R95") (pin "1") (pinfunction "1_1") (pintype "passive"))
      (node (ref "U5") (pin "12") (pinfunction "D+_12") (pintype "passive"))
    )
    (net (code "125") (name "Net-(U5D-D-)") (class "Default")
      (node (ref "R78") (pin "1") (pinfunction "1_1") (pintype "passive"))
      (node (ref "R79") (pin "2") (pinfunction "2_2") (pintype "passive"))
      (node (ref "U5") (pin "13") (pinfunction "D-_13") (pintype "passive"))
    )
    (net (code "126") (name "Net-(U5D-D_O)") (class "Default")
      (node (ref "R79") (pin "1") (pinfunction "1_1") (pintype "passive"))
      (node (ref "R86") (pin "2") (pinfunction "2_2") (pintype "passive"))
      (node (ref "U5") (pin "14") (pinfunction "D_O_14") (pintype "passive"))
    )
    (net (code "127") (name "STAR") (class "Default")
      (node (ref "JP2") (pin "7") (pinfunction "7_7") (pintype "passive"))
      (node (ref "R82") (pin "1") (pinfunction "1_1") (pintype "passive"))
      (node (ref "R83") (pin "1") (pinfunction "1_1") (pintype "passive"))
      (node (ref "R92") (pin "1") (pinfunction "1_1") (pintype "passive"))
    )
    (net (code "128") (name "SUM_CURR") (class "Default")
      (node (ref "J41") (pin "1") (pinfunction "1_1") (pintype "passive"))
      (node (ref "JP1") (pin "14") (pinfunction "14_14") (pintype "passive"))
      (node (ref "R87") (pin "1") (pinfunction "1_1") (pintype "passive"))
    )
    (net (code "129") (name "SUM_I") (class "Default")
      (node (ref "C28") (pin "2") (pinfunction "2_2") (pintype "passive"))
      (node (ref "C29") (pin "2") (pinfunction "2_2") (pintype "passive"))
      (node (ref "C30") (pin "2") (pinfunction "2_2") (pintype "passive"))
      (node (ref "J33") (pin "1") (pinfunction "1_1") (pintype "passive"))
      (node (ref "J34") (pin "1") (pinfunction "1_1") (pintype "passive"))
      (node (ref "J37") (pin "1") (pinfunction "1_1") (pintype "passive"))
      (node (ref "M6") (pin "3") (pinfunction "SOURCE_3") (pintype "passive"))
      (node (ref "R109") (pin "2") (pinfunction "2_2") (pintype "passive"))
      (node (ref "R110") (pin "2") (pinfunction "2_2") (pintype "passive"))
      (node (ref "R115") (pin "2") (pinfunction "2_2") (pintype "passive"))
      (node (ref "R56") (pin "1") (pinfunction "1_1") (pintype "passive"))
      (node (ref "R64") (pin "2") (pinfunction "2_2") (pintype "passive"))
      (node (ref "R65") (pin "2") (pinfunction "2_2") (pintype "passive"))
      (node (ref "R70") (pin "1") (pinfunction "1_1") (pintype "passive"))
    )
    (net (code "130") (name "U") (class "Default")
      (node (ref "J14") (pin "12") (pinfunction "12_12") (pintype "passive"))
      (node (ref "J14") (pin "13") (pinfunction "13_13") (pintype "passive"))
      (node (ref "J14") (pin "14") (pinfunction "14_14") (pintype "passive"))
      (node (ref "J17") (pin "1") (pinfunction "1_1") (pintype "passive"))
      (node (ref "J22") (pin "1") (pinfunction "1_1") (pintype "passive"))
      (node (ref "JP3") (pin "3") (pinfunction "3_3") (pintype "passive"))
      (node (ref "M1") (pin "3") (pinfunction "SOURCE_3") (pintype "passive"))
      (node (ref "M4") (pin "2") (pinfunction "DRAIN_2") (pintype "passive"))
      (node (ref "R43") (pin "2") (pinfunction "2_2") (pintype "passive"))
      (node (ref "R71") (pin "2") (pinfunction "2_2") (pintype "passive"))
    )
    (net (code "131") (name "U_CURR") (class "Default")
      (node (ref "J39") (pin "1") (pinfunction "1_1") (pintype "passive"))
      (node (ref "JP1") (pin "11") (pinfunction "11_11") (pintype "passive"))
      (node (ref "R85") (pin "1") (pinfunction "1_1") (pintype "passive"))
    )
    (net (code "132") (name "U_EMF") (class "Default")
      (node (ref "J10") (pin "1") (pinfunction "1_1") (pintype "passive"))
      (node (ref "JP2") (pin "3") (pinfunction "3_3") (pintype "passive"))
      (node (ref "R71") (pin "1") (pinfunction "1_1") (pintype "passive"))
      (node (ref "R82") (pin "2") (pinfunction "2_2") (pintype "passive"))
      (node (ref "R97") (pin "2") (pinfunction "2_2") (pintype "passive"))
    )
    (net (code "133") (name "U_I") (class "Default")
      (node (ref "J30") (pin "1") (pinfunction "1_1") (pintype "passive"))
      (node (ref "M4") (pin "3") (pinfunction "SOURCE_3") (pintype "passive"))
      (node (ref "R113") (pin "2") (pinfunction "2_2") (pintype "passive"))
      (node (ref "R54") (pin "1") (pinfunction "1_1") (pintype "passive"))
      (node (ref "R64") (pin "1") (pinfunction "1_1") (pintype "passive"))
    )
    (net (code "134") (name "V") (class "Default")
      (node (ref "J14") (pin "10") (pinfunction "10_10") (pintype "passive"))
      (node (ref "J14") (pin "11") (pinfunction "11_11") (pintype "passive"))
      (node (ref "J14") (pin "9") (pinfunction "9_9") (pintype "passive"))
      (node (ref "J17") (pin "2") (pinfunction "2_2") (pintype "passive"))
      (node (ref "J23") (pin "1") (pinfunction "1_1") (pintype "passive"))
      (node (ref "JP3") (pin "9") (pinfunction "9_9") (pintype "passive"))
      (node (ref "M2") (pin "3") (pinfunction "SOURCE_3") (pintype "passive"))
      (node (ref "M5") (pin "2") (pinfunction "DRAIN_2") (pintype "passive"))
      (node (ref "R44") (pin "2") (pinfunction "2_2") (pintype "passive"))
      (node (ref "R72") (pin "2") (pinfunction "2_2") (pintype "passive"))
    )
    (net (code "135") (name "V_CURR") (class "Default")
      (node (ref "J40") (pin "1") (pinfunction "1_1") (pintype "passive"))
      (node (ref "JP1") (pin "12") (pinfunction "12_12") (pintype "passive"))
      (node (ref "R86") (pin "1") (pinfunction "1_1") (pintype "passive"))
    )
    (net (code "136") (name "V_EMF") (class "Default")
      (node (ref "J11") (pin "1") (pinfunction "1_1") (pintype "passive"))
      (node (ref "JP2") (pin "5") (pinfunction "5_5") (pintype "passive"))
      (node (ref "R72") (pin "1") (pinfunction "1_1") (pintype "passive"))
      (node (ref "R83") (pin "2") (pinfunction "2_2") (pintype "passive"))
      (node (ref "R98") (pin "2") (pinfunction "2_2") (pintype "passive"))
    )
    (net (code "137") (name "V_I") (class "Default")
      (node (ref "J31") (pin "1") (pinfunction "1_1") (pintype "passive"))
      (node (ref "M5") (pin "3") (pinfunction "SOURCE_3") (pintype "passive"))
      (node (ref "R114") (pin "2") (pinfunction "2_2") (pintype "passive"))
      (node (ref "R55") (pin "1") (pinfunction "1_1") (pintype "passive"))
      (node (ref "R65") (pin "1") (pinfunction "1_1") (pintype "passive"))
    )
    (net (code "138") (name "W") (class "Default")
      (node (ref "J14") (pin "6") (pinfunction "6_6") (pintype "passive"))
      (node (ref "J14") (pin "7") (pinfunction "7_7") (pintype "passive"))
      (node (ref "J14") (pin "8") (pinfunction "8_8") (pintype "passive"))
      (node (ref "J17") (pin "3") (pinfunction "3_3") (pintype "passive"))
      (node (ref "J24") (pin "1") (pinfunction "1_1") (pintype "passive"))
      (node (ref "JP3") (pin "15") (pinfunction "15_15") (pintype "passive"))
      (node (ref "M3") (pin "3") (pinfunction "SOURCE_3") (pintype "passive"))
      (node (ref "M6") (pin "2") (pinfunction "DRAIN_2") (pintype "passive"))
      (node (ref "R45") (pin "2") (pinfunction "2_2") (pintype "passive"))
      (node (ref "R73") (pin "2") (pinfunction "2_2") (pintype "passive"))
    )
    (net (code "139") (name "W_EMF") (class "Default")
      (node (ref "J15") (pin "1") (pinfunction "1_1") (pintype "passive"))
      (node (ref "JP2") (pin "9") (pinfunction "9_9") (pintype "passive"))
      (node (ref "R73") (pin "1") (pinfunction "1_1") (pintype "passive"))
      (node (ref "R92") (pin "2") (pinfunction "2_2") (pintype "passive"))
      (node (ref "R99") (pin "2") (pinfunction "2_2") (pintype "passive"))
    )
    (net (code "140") (name "unconnected-(JP4-Pad5)") (class "Default")
      (node (ref "JP4") (pin "5") (pinfunction "5_5") (pintype "passive"))
    )
    (net (code "141") (name "unconnected-(JP4-Pad6)") (class "Default")
      (node (ref "JP4") (pin "6") (pinfunction "6_6") (pintype "passive"))
    )
  )
)
